# LED_panel_rev3_15.net
KiCad netlist of a schematic drawn in EAGLE
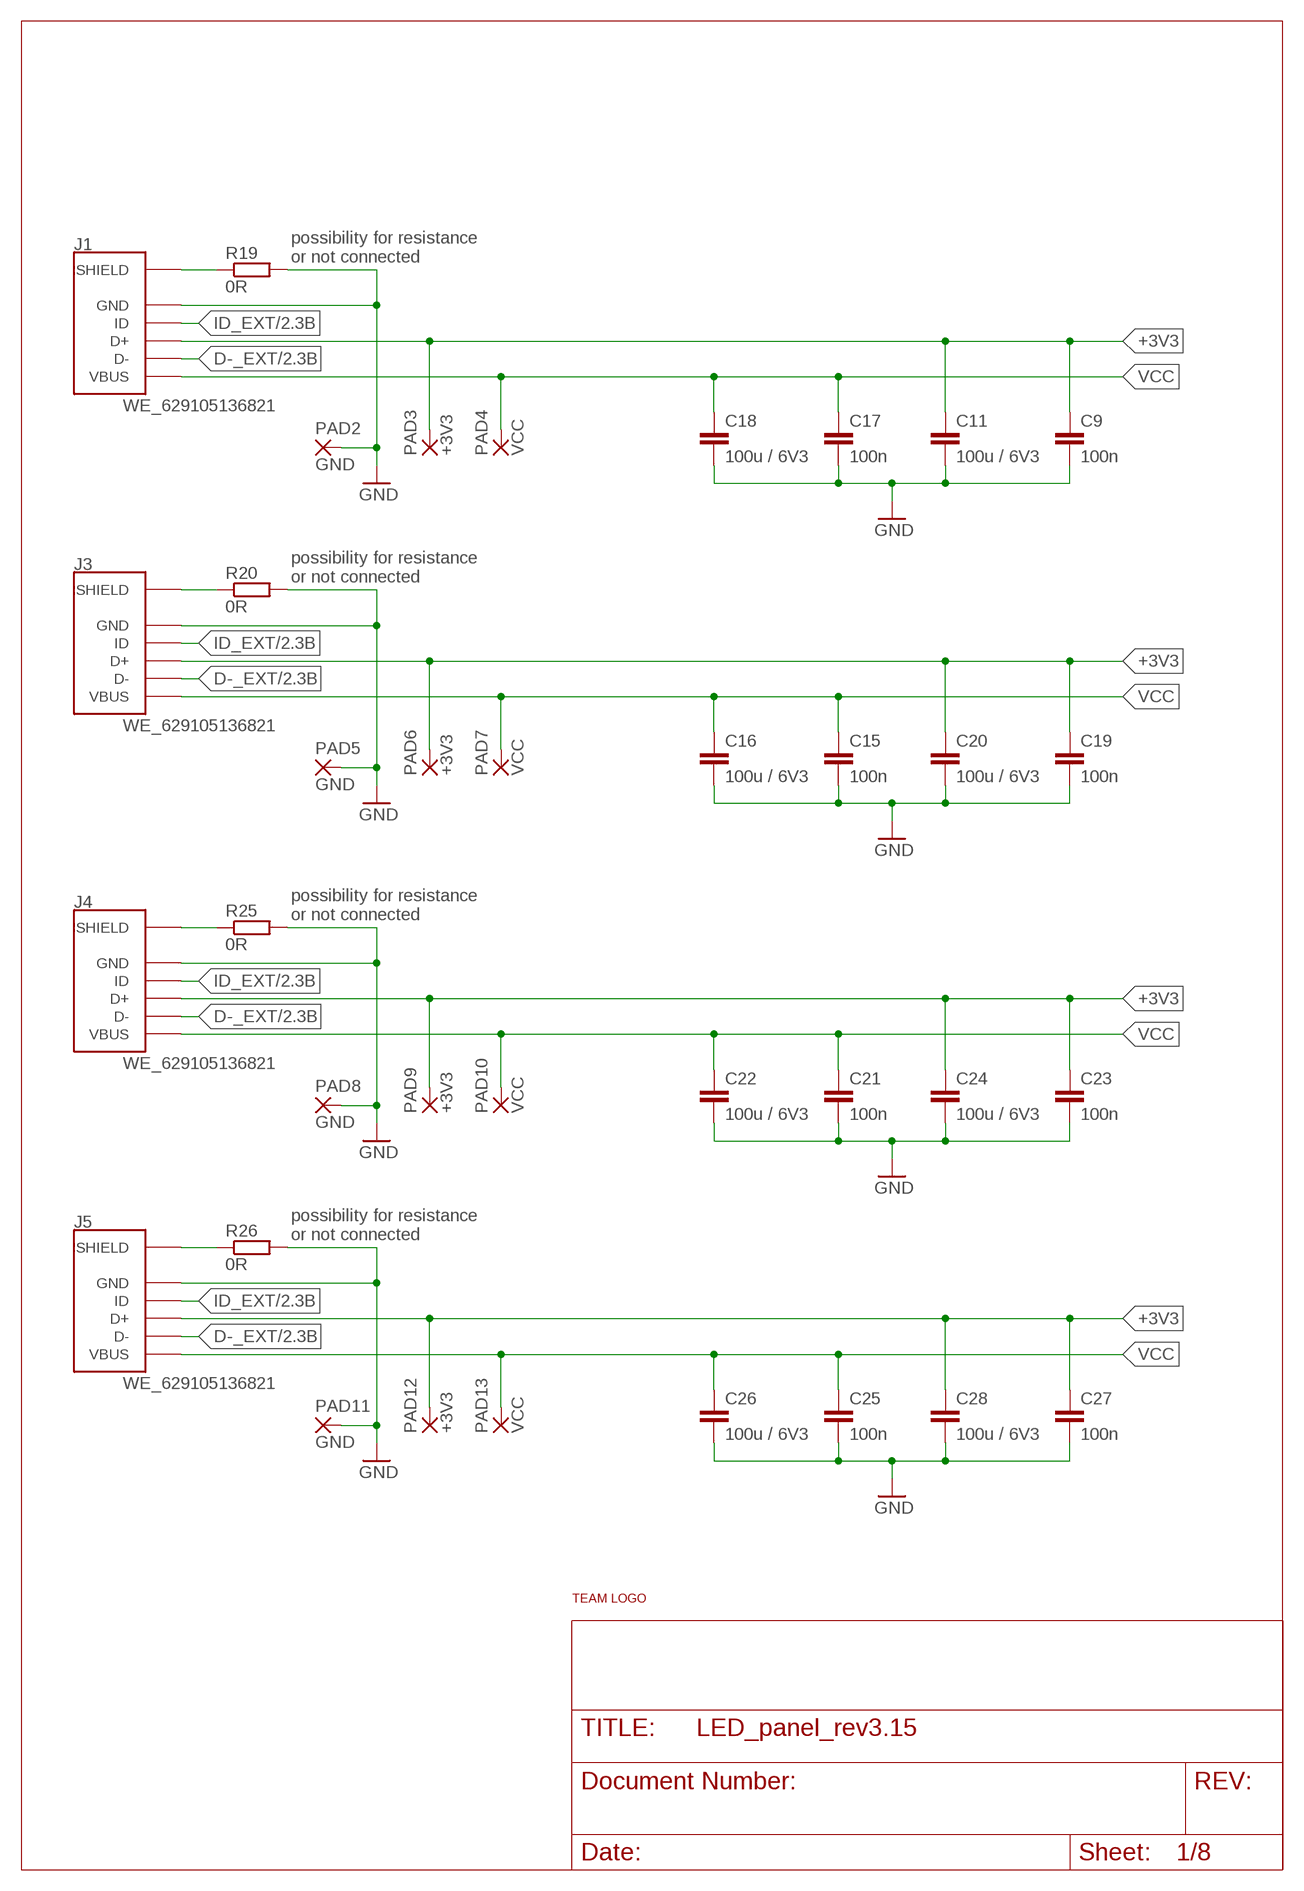
[diagram p0: schematic, sheet 1]
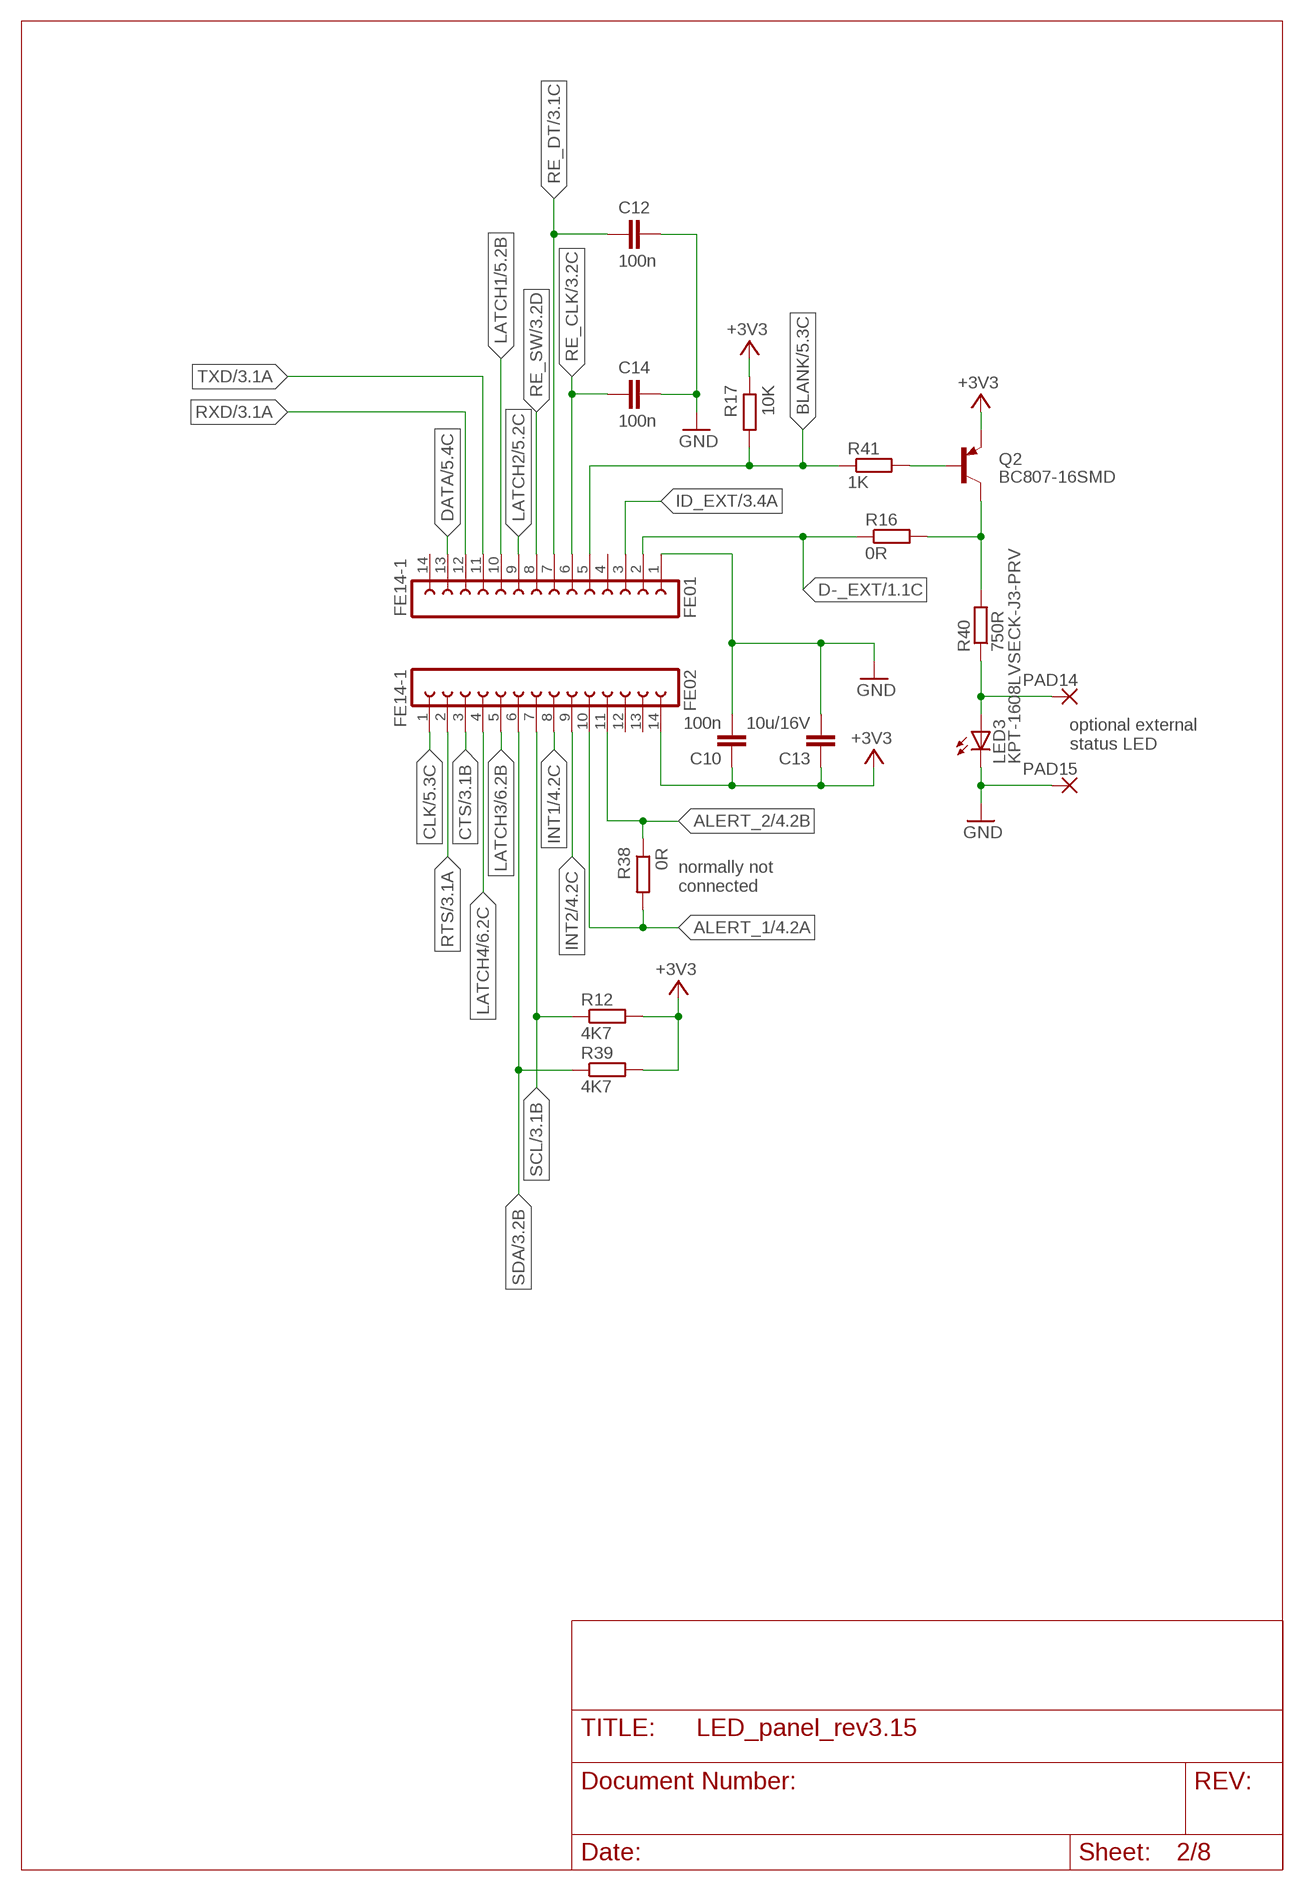
[diagram p1: schematic, sheet 2]
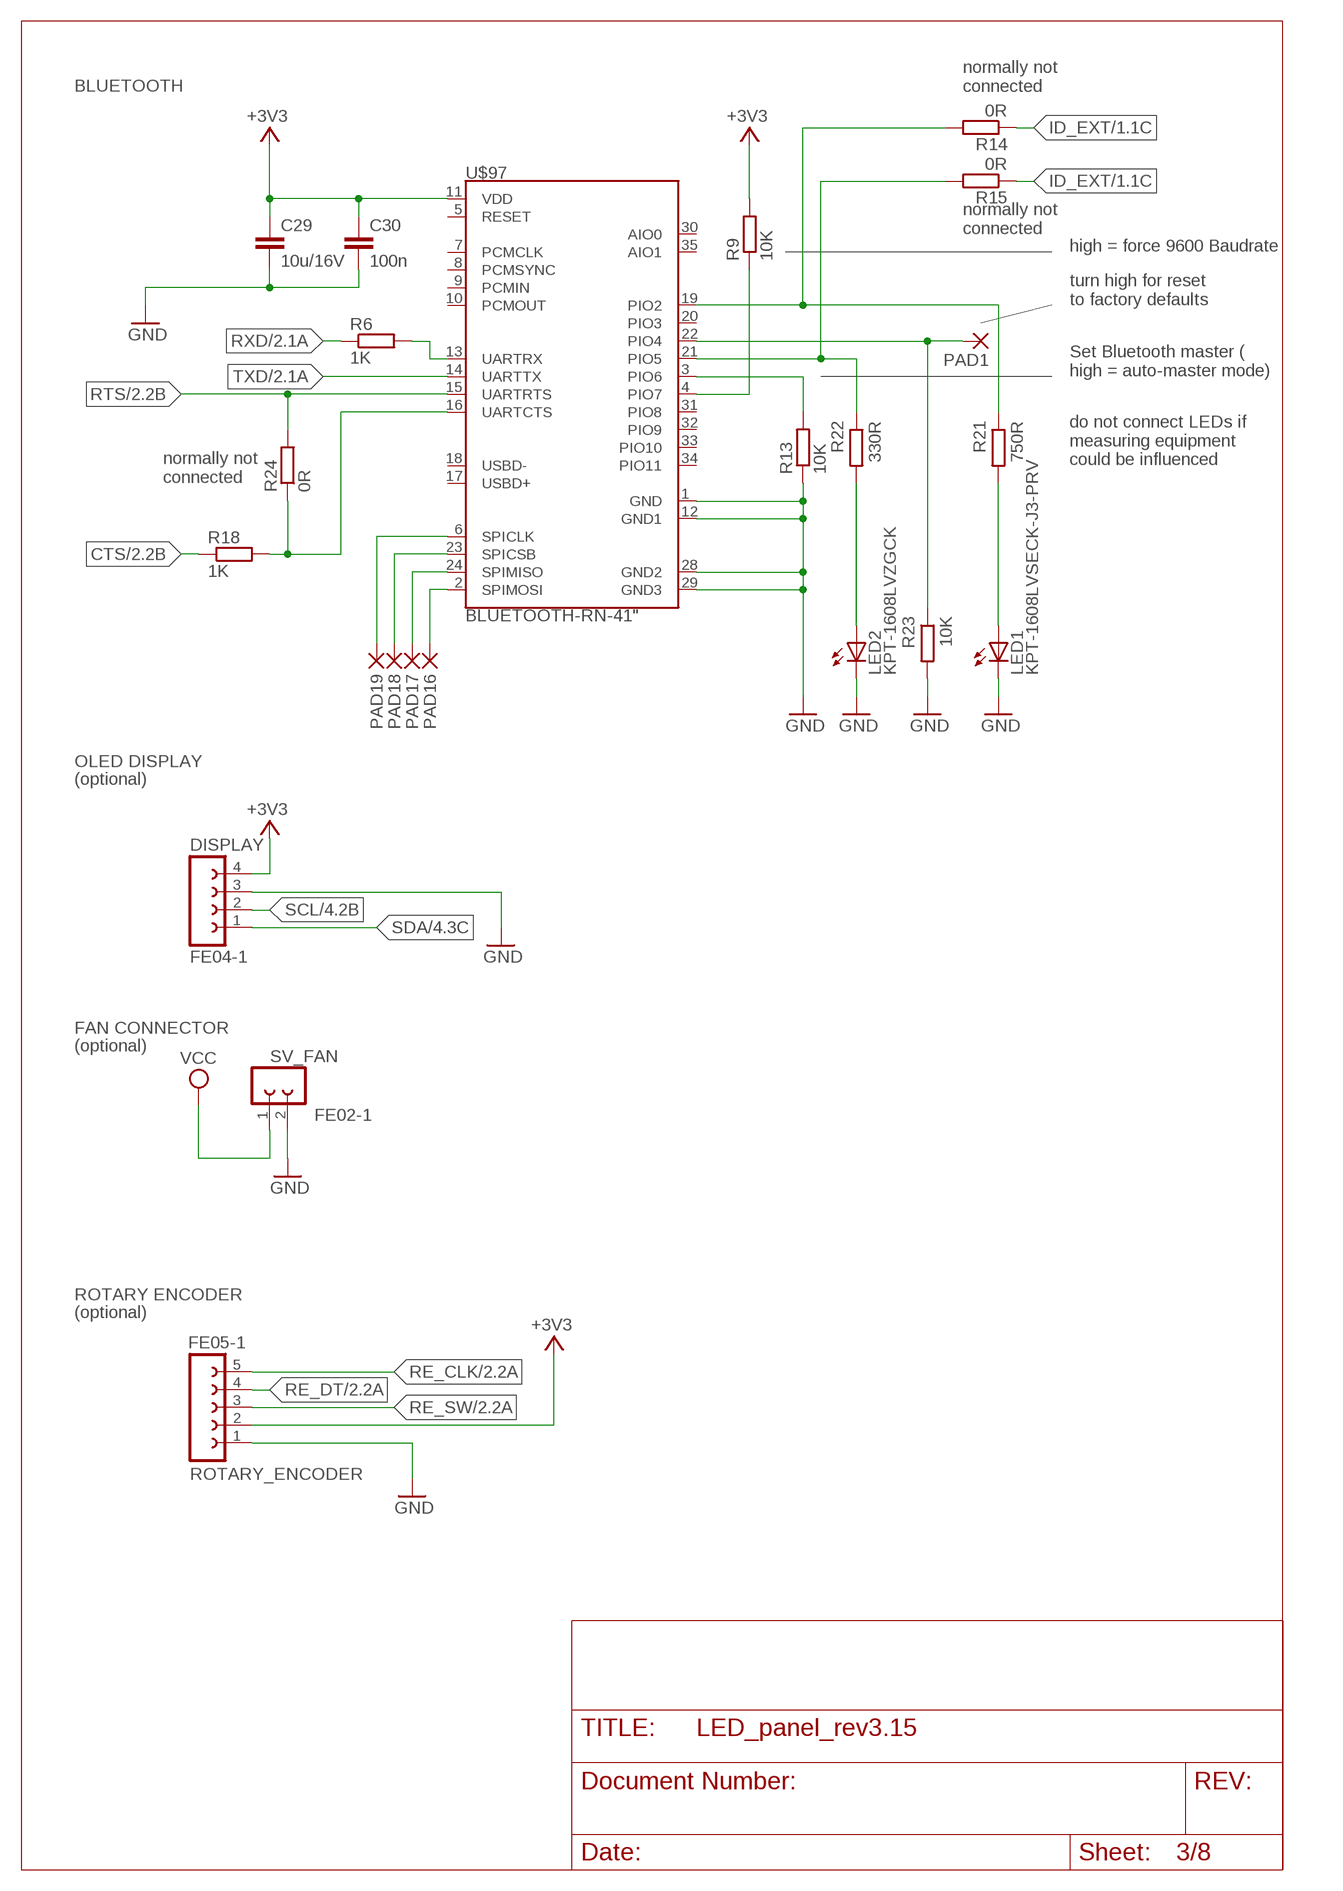
[diagram p2: schematic, sheet 3]
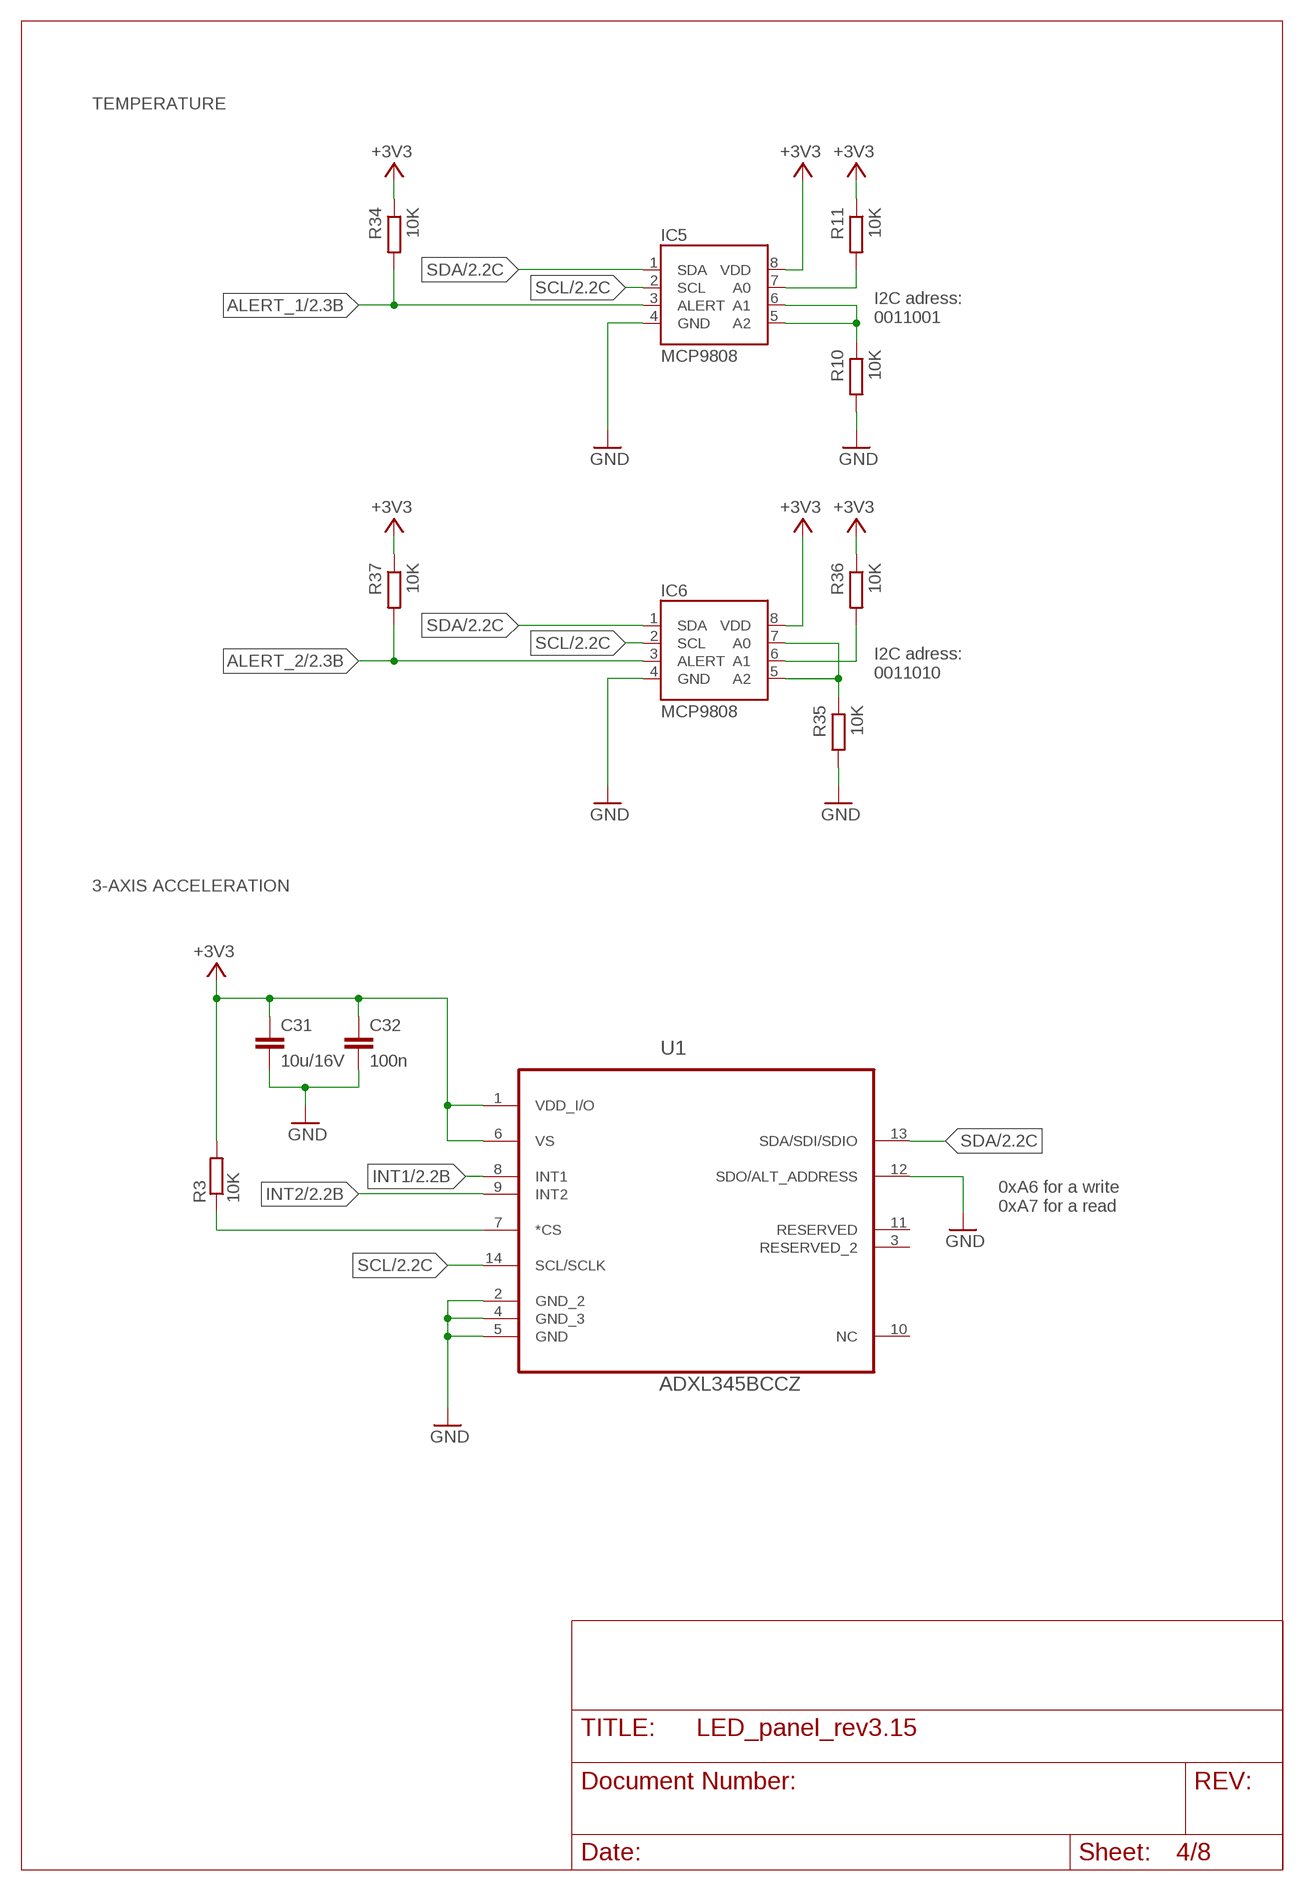
[diagram p3: schematic, sheet 4]
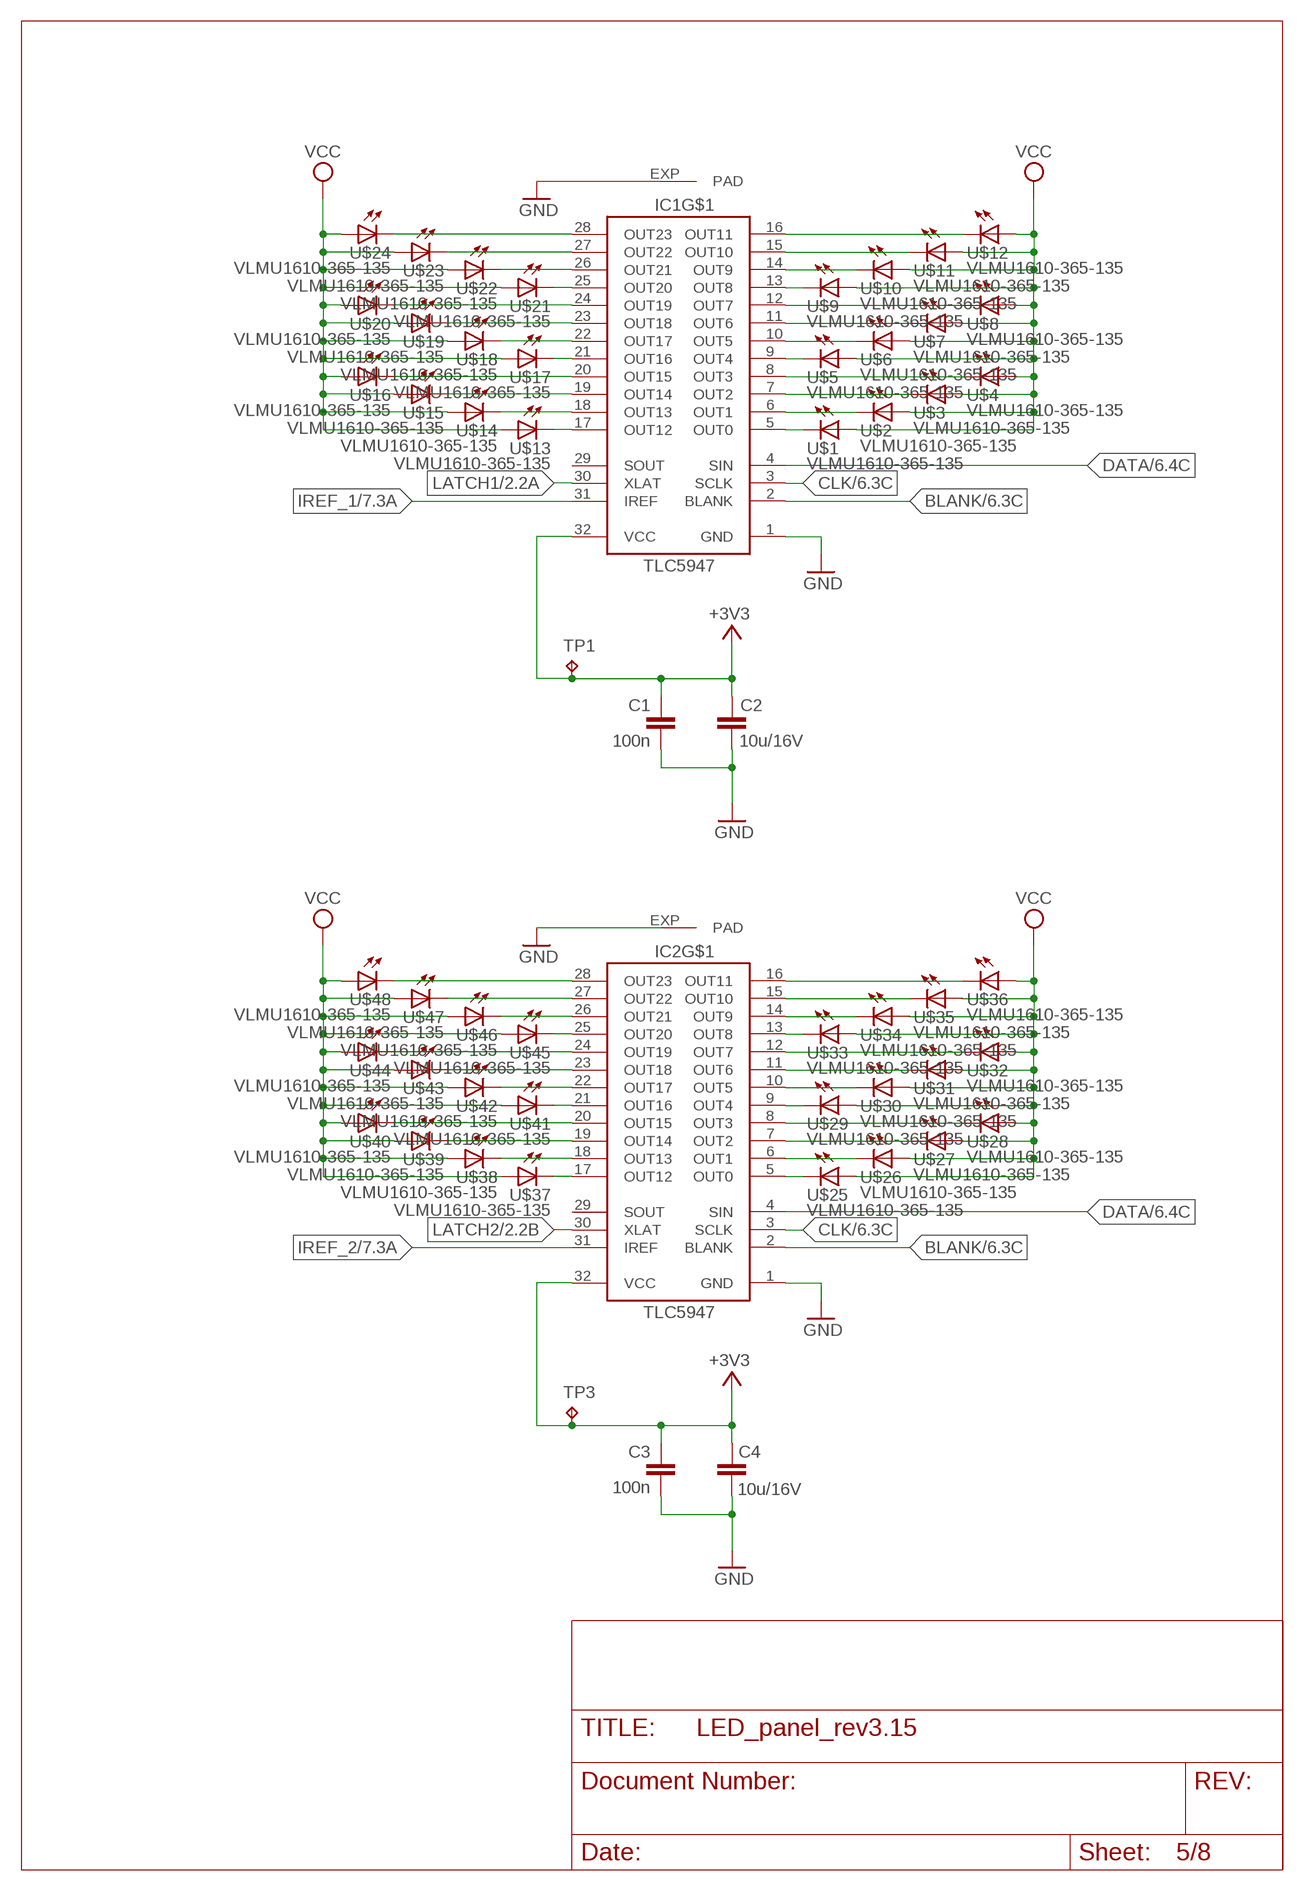
[diagram p4: schematic, sheet 5]
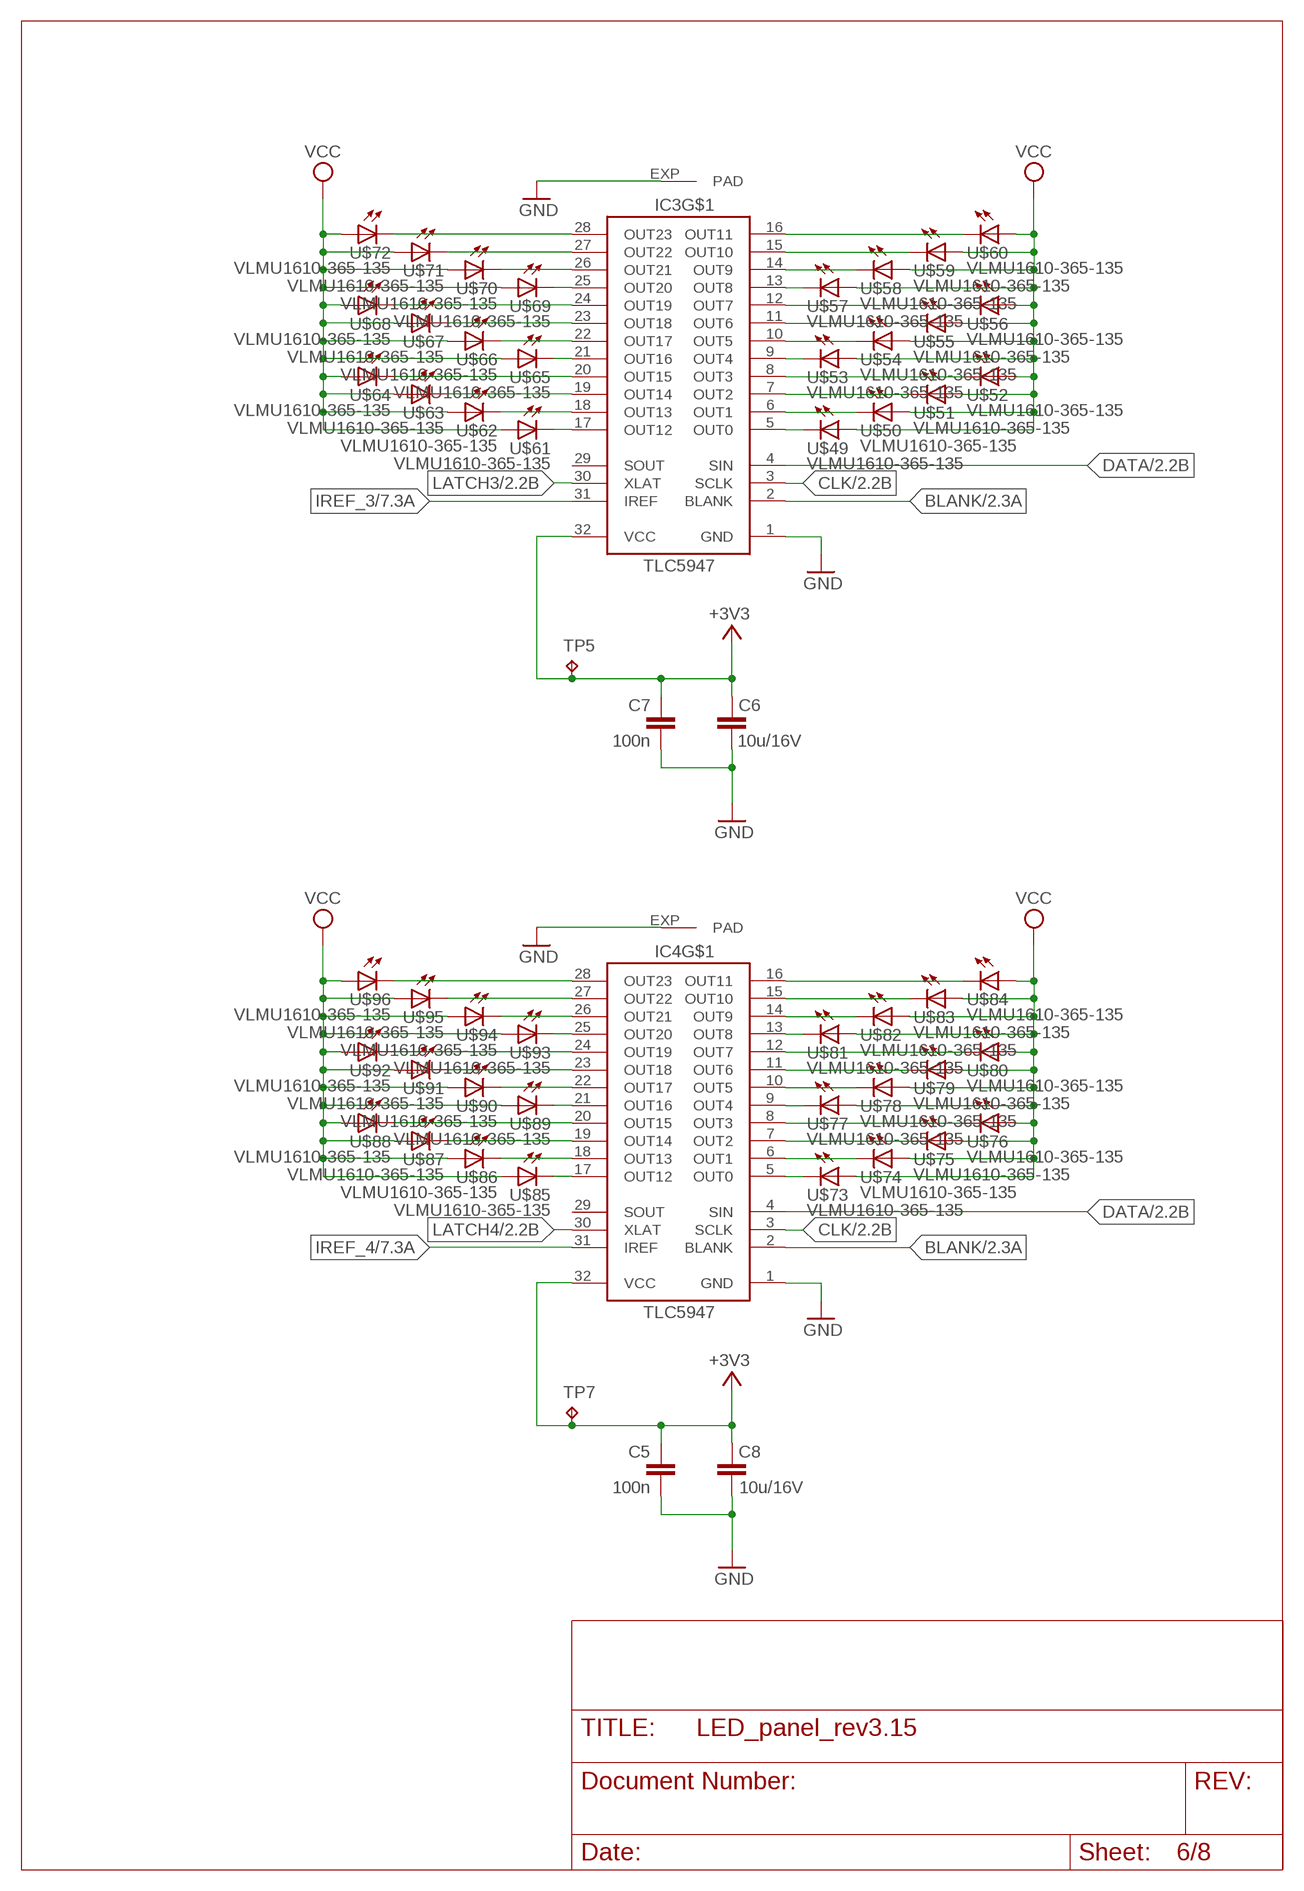
[diagram p5: schematic, sheet 6]
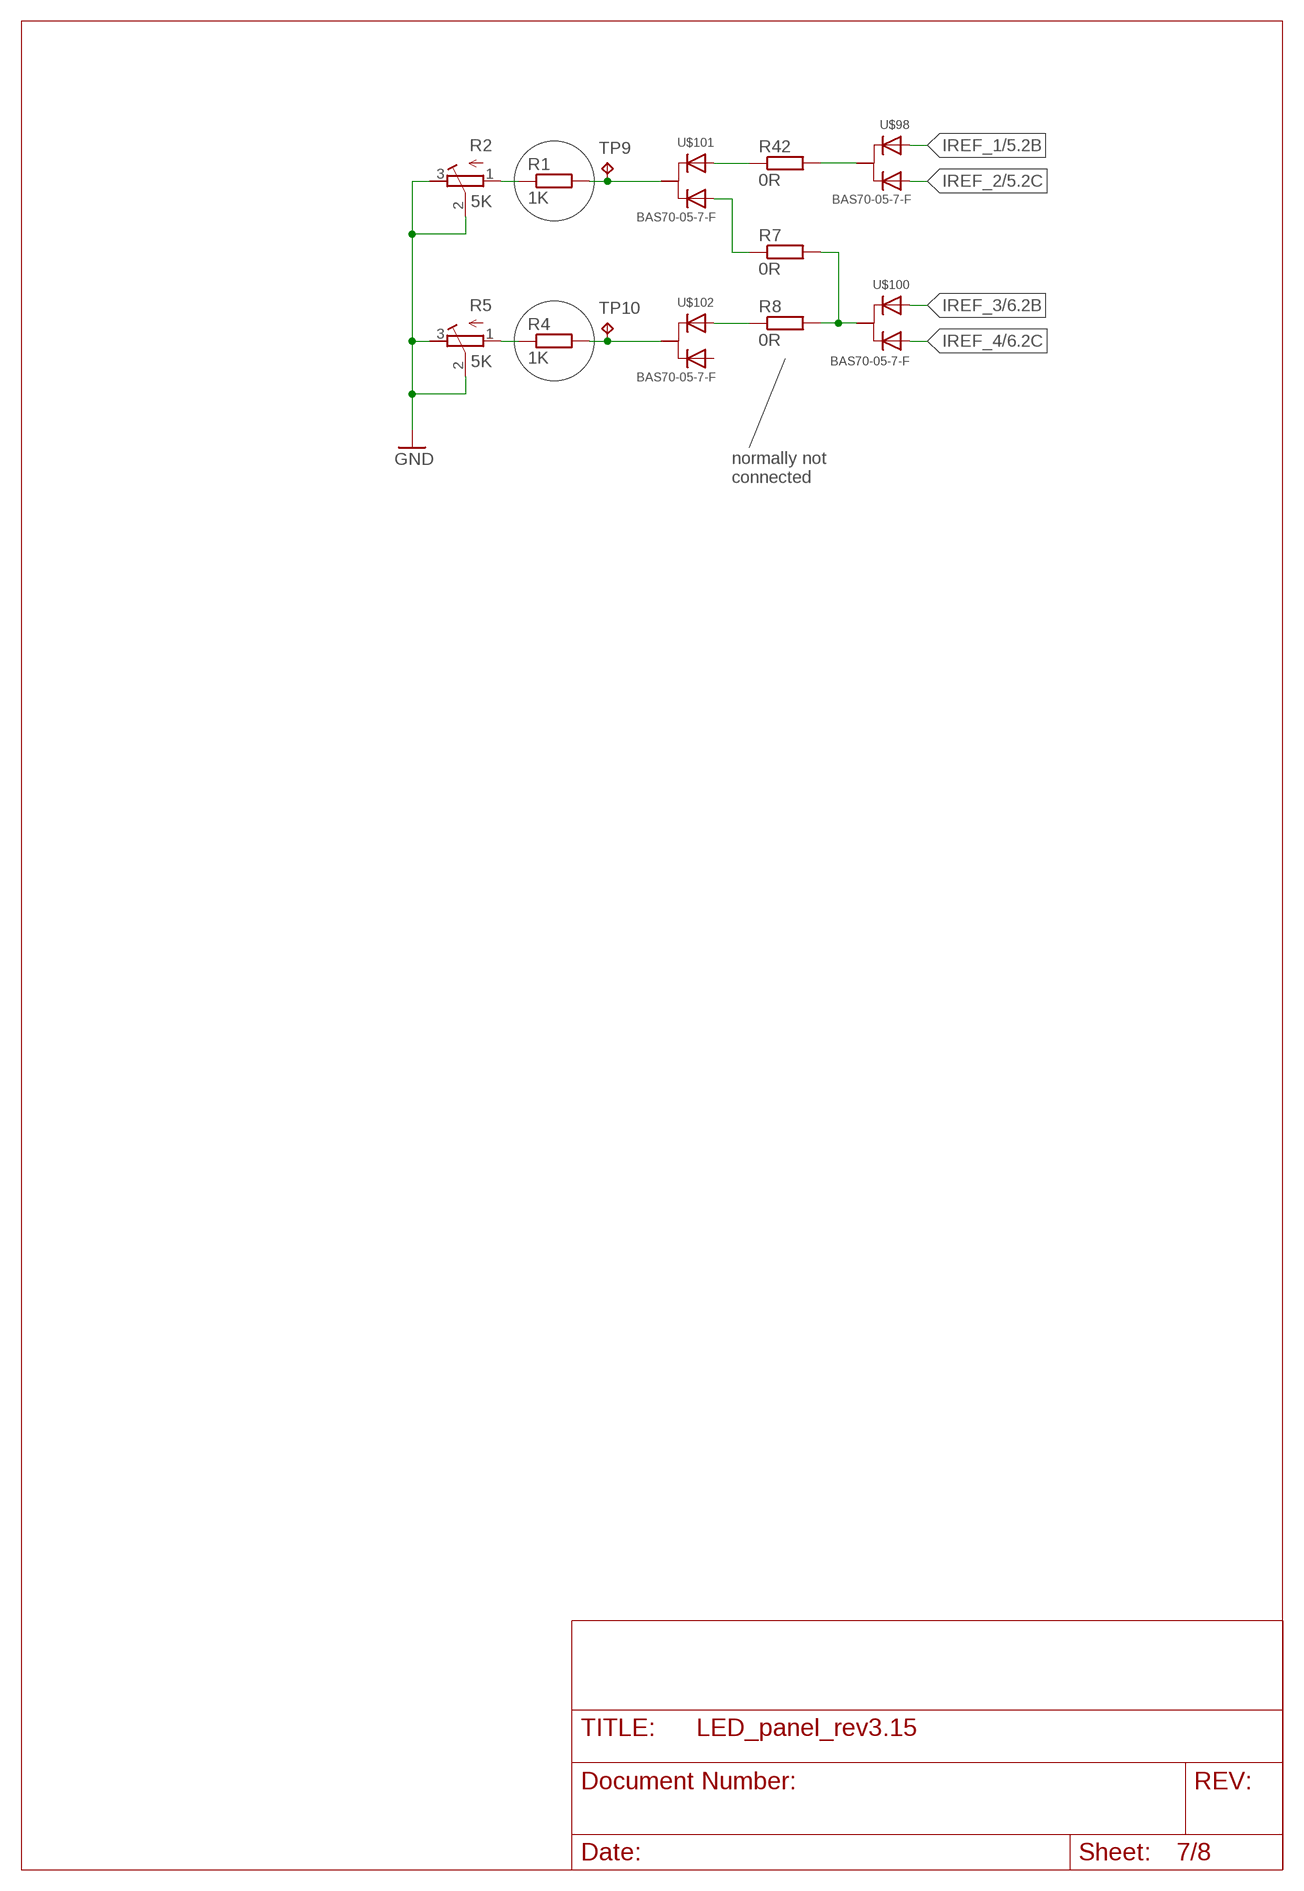
[diagram p6: schematic, sheet 7]

(export (version "E")
  (design (tool "Eeschema 10.0.6"))
  (components
    (comp (ref "C31")
      (value "10u/16V")
      (footprint "eagle-import:C1206K")
      (libsource (lib "eagle-import") (part "C-EUC1206K"))
    )
    (comp (ref "C32")
      (value "100n")
      (footprint "eagle-import:C1206K")
      (libsource (lib "eagle-import") (part "C-EUC1206K"))
    )
    (comp (ref "IC5")
      (value "MCP9808")
      (footprint "eagle-import:MSOP8")
      (libsource (lib "eagle-import") (part "MCP9808"))
    )
    (comp (ref "IC6")
      (value "MCP9808")
      (footprint "eagle-import:MSOP8")
      (libsource (lib "eagle-import") (part "MCP9808"))
    )
    (comp (ref "R3")
      (value "10K")
      (footprint "eagle-import:R1206")
      (libsource (lib "eagle-import") (part "R-EU_R1206"))
    )
    (comp (ref "R10")
      (value "10K")
      (footprint "eagle-import:R1206")
      (libsource (lib "eagle-import") (part "R-EU_R1206"))
    )
    (comp (ref "R11")
      (value "10K")
      (footprint "eagle-import:R1206")
      (libsource (lib "eagle-import") (part "R-EU_R1206"))
    )
    (comp (ref "R34")
      (value "10K")
      (footprint "eagle-import:R1206")
      (libsource (lib "eagle-import") (part "R-EU_R1206"))
    )
    (comp (ref "R35")
      (value "10K")
      (footprint "eagle-import:R1206")
      (libsource (lib "eagle-import") (part "R-EU_R1206"))
    )
    (comp (ref "R36")
      (value "10K")
      (footprint "eagle-import:R1206")
      (libsource (lib "eagle-import") (part "R-EU_R1206"))
    )
    (comp (ref "R37")
      (value "10K")
      (footprint "eagle-import:R1206")
      (libsource (lib "eagle-import") (part "R-EU_R1206"))
    )
    (comp (ref "U1")
      (value "ADXL345BCCZ")
      (footprint "eagle-import:LGA14R80P3X6_300X500X100")
      (libsource (lib "eagle-import") (part "ADXL345BCCZ"))
    )
    (comp (ref "C1")
      (value "100n")
      (footprint "eagle-import:C1206K")
      (libsource (lib "eagle-import") (part "C-EUC1206K"))
    )
    (comp (ref "C2")
      (value "10u/16V")
      (footprint "eagle-import:C1206K")
      (libsource (lib "eagle-import") (part "C-EUC1206K"))
    )
    (comp (ref "C3")
      (value "100n")
      (footprint "eagle-import:C1206K")
      (libsource (lib "eagle-import") (part "C-EUC1206K"))
    )
    (comp (ref "C4")
      (value "10u/16V")
      (footprint "eagle-import:C1206K")
      (libsource (lib "eagle-import") (part "C-EUC1206K"))
    )
    (comp (ref "IC1")
      (value "TLC5947-DAP")
      (footprint "eagle-import:HTSSOP32DAP")
      (libsource (lib "eagle-import") (part "TLC5947-DAP"))
    )
    (comp (ref "IC2")
      (value "TLC5947-DAP")
      (footprint "eagle-import:HTSSOP32DAP")
      (libsource (lib "eagle-import") (part "TLC5947-DAP"))
    )
    (comp (ref "TP1")
      (value "TPTP20R")
      (footprint "eagle-import:TP20R")
      (libsource (lib "eagle-import") (part "TPTP20R"))
    )
    (comp (ref "TP3")
      (value "TPTP20R")
      (footprint "eagle-import:TP20R")
      (libsource (lib "eagle-import") (part "TPTP20R"))
    )
    (comp (ref "U$1")
      (value "VLMU1610-365-135")
      (footprint "eagle-import:SMD_CERAMIC_MID_POWER")
      (libsource (lib "eagle-import") (part "VLMU1610-365-135"))
    )
    (comp (ref "U$2")
      (value "VLMU1610-365-135")
      (footprint "eagle-import:SMD_CERAMIC_MID_POWER")
      (libsource (lib "eagle-import") (part "VLMU1610-365-135"))
    )
    (comp (ref "U$3")
      (value "VLMU1610-365-135")
      (footprint "eagle-import:SMD_CERAMIC_MID_POWER")
      (libsource (lib "eagle-import") (part "VLMU1610-365-135"))
    )
    (comp (ref "U$4")
      (value "VLMU1610-365-135")
      (footprint "eagle-import:SMD_CERAMIC_MID_POWER")
      (libsource (lib "eagle-import") (part "VLMU1610-365-135"))
    )
    (comp (ref "U$5")
      (value "VLMU1610-365-135")
      (footprint "eagle-import:SMD_CERAMIC_MID_POWER")
      (libsource (lib "eagle-import") (part "VLMU1610-365-135"))
    )
    (comp (ref "U$6")
      (value "VLMU1610-365-135")
      (footprint "eagle-import:SMD_CERAMIC_MID_POWER")
      (libsource (lib "eagle-import") (part "VLMU1610-365-135"))
    )
    (comp (ref "U$7")
      (value "VLMU1610-365-135")
      (footprint "eagle-import:SMD_CERAMIC_MID_POWER")
      (libsource (lib "eagle-import") (part "VLMU1610-365-135"))
    )
    (comp (ref "U$8")
      (value "VLMU1610-365-135")
      (footprint "eagle-import:SMD_CERAMIC_MID_POWER")
      (libsource (lib "eagle-import") (part "VLMU1610-365-135"))
    )
    (comp (ref "U$9")
      (value "VLMU1610-365-135")
      (footprint "eagle-import:SMD_CERAMIC_MID_POWER")
      (libsource (lib "eagle-import") (part "VLMU1610-365-135"))
    )
    (comp (ref "U$10")
      (value "VLMU1610-365-135")
      (footprint "eagle-import:SMD_CERAMIC_MID_POWER")
      (libsource (lib "eagle-import") (part "VLMU1610-365-135"))
    )
    (comp (ref "U$11")
      (value "VLMU1610-365-135")
      (footprint "eagle-import:SMD_CERAMIC_MID_POWER")
      (libsource (lib "eagle-import") (part "VLMU1610-365-135"))
    )
    (comp (ref "U$12")
      (value "VLMU1610-365-135")
      (footprint "eagle-import:SMD_CERAMIC_MID_POWER")
      (libsource (lib "eagle-import") (part "VLMU1610-365-135"))
    )
    (comp (ref "U$13")
      (value "VLMU1610-365-135")
      (footprint "eagle-import:SMD_CERAMIC_MID_POWER")
      (libsource (lib "eagle-import") (part "VLMU1610-365-135"))
    )
    (comp (ref "U$14")
      (value "VLMU1610-365-135")
      (footprint "eagle-import:SMD_CERAMIC_MID_POWER")
      (libsource (lib "eagle-import") (part "VLMU1610-365-135"))
    )
    (comp (ref "U$15")
      (value "VLMU1610-365-135")
      (footprint "eagle-import:SMD_CERAMIC_MID_POWER")
      (libsource (lib "eagle-import") (part "VLMU1610-365-135"))
    )
    (comp (ref "U$16")
      (value "VLMU1610-365-135")
      (footprint "eagle-import:SMD_CERAMIC_MID_POWER")
      (libsource (lib "eagle-import") (part "VLMU1610-365-135"))
    )
    (comp (ref "U$17")
      (value "VLMU1610-365-135")
      (footprint "eagle-import:SMD_CERAMIC_MID_POWER")
      (libsource (lib "eagle-import") (part "VLMU1610-365-135"))
    )
    (comp (ref "U$18")
      (value "VLMU1610-365-135")
      (footprint "eagle-import:SMD_CERAMIC_MID_POWER")
      (libsource (lib "eagle-import") (part "VLMU1610-365-135"))
    )
    (comp (ref "U$19")
      (value "VLMU1610-365-135")
      (footprint "eagle-import:SMD_CERAMIC_MID_POWER")
      (libsource (lib "eagle-import") (part "VLMU1610-365-135"))
    )
    (comp (ref "U$20")
      (value "VLMU1610-365-135")
      (footprint "eagle-import:SMD_CERAMIC_MID_POWER")
      (libsource (lib "eagle-import") (part "VLMU1610-365-135"))
    )
    (comp (ref "U$21")
      (value "VLMU1610-365-135")
      (footprint "eagle-import:SMD_CERAMIC_MID_POWER")
      (libsource (lib "eagle-import") (part "VLMU1610-365-135"))
    )
    (comp (ref "U$22")
      (value "VLMU1610-365-135")
      (footprint "eagle-import:SMD_CERAMIC_MID_POWER")
      (libsource (lib "eagle-import") (part "VLMU1610-365-135"))
    )
    (comp (ref "U$23")
      (value "VLMU1610-365-135")
      (footprint "eagle-import:SMD_CERAMIC_MID_POWER")
      (libsource (lib "eagle-import") (part "VLMU1610-365-135"))
    )
    (comp (ref "U$24")
      (value "VLMU1610-365-135")
      (footprint "eagle-import:SMD_CERAMIC_MID_POWER")
      (libsource (lib "eagle-import") (part "VLMU1610-365-135"))
    )
    (comp (ref "U$25")
      (value "VLMU1610-365-135")
      (footprint "eagle-import:SMD_CERAMIC_MID_POWER")
      (libsource (lib "eagle-import") (part "VLMU1610-365-135"))
    )
    (comp (ref "U$26")
      (value "VLMU1610-365-135")
      (footprint "eagle-import:SMD_CERAMIC_MID_POWER")
      (libsource (lib "eagle-import") (part "VLMU1610-365-135"))
    )
    (comp (ref "U$27")
      (value "VLMU1610-365-135")
      (footprint "eagle-import:SMD_CERAMIC_MID_POWER")
      (libsource (lib "eagle-import") (part "VLMU1610-365-135"))
    )
    (comp (ref "U$28")
      (value "VLMU1610-365-135")
      (footprint "eagle-import:SMD_CERAMIC_MID_POWER")
      (libsource (lib "eagle-import") (part "VLMU1610-365-135"))
    )
    (comp (ref "U$29")
      (value "VLMU1610-365-135")
      (footprint "eagle-import:SMD_CERAMIC_MID_POWER")
      (libsource (lib "eagle-import") (part "VLMU1610-365-135"))
    )
    (comp (ref "U$30")
      (value "VLMU1610-365-135")
      (footprint "eagle-import:SMD_CERAMIC_MID_POWER")
      (libsource (lib "eagle-import") (part "VLMU1610-365-135"))
    )
    (comp (ref "U$31")
      (value "VLMU1610-365-135")
      (footprint "eagle-import:SMD_CERAMIC_MID_POWER")
      (libsource (lib "eagle-import") (part "VLMU1610-365-135"))
    )
    (comp (ref "U$32")
      (value "VLMU1610-365-135")
      (footprint "eagle-import:SMD_CERAMIC_MID_POWER")
      (libsource (lib "eagle-import") (part "VLMU1610-365-135"))
    )
    (comp (ref "U$33")
      (value "VLMU1610-365-135")
      (footprint "eagle-import:SMD_CERAMIC_MID_POWER")
      (libsource (lib "eagle-import") (part "VLMU1610-365-135"))
    )
    (comp (ref "U$34")
      (value "VLMU1610-365-135")
      (footprint "eagle-import:SMD_CERAMIC_MID_POWER")
      (libsource (lib "eagle-import") (part "VLMU1610-365-135"))
    )
    (comp (ref "U$35")
      (value "VLMU1610-365-135")
      (footprint "eagle-import:SMD_CERAMIC_MID_POWER")
      (libsource (lib "eagle-import") (part "VLMU1610-365-135"))
    )
    (comp (ref "U$36")
      (value "VLMU1610-365-135")
      (footprint "eagle-import:SMD_CERAMIC_MID_POWER")
      (libsource (lib "eagle-import") (part "VLMU1610-365-135"))
    )
    (comp (ref "U$37")
      (value "VLMU1610-365-135")
      (footprint "eagle-import:SMD_CERAMIC_MID_POWER")
      (libsource (lib "eagle-import") (part "VLMU1610-365-135"))
    )
    (comp (ref "U$38")
      (value "VLMU1610-365-135")
      (footprint "eagle-import:SMD_CERAMIC_MID_POWER")
      (libsource (lib "eagle-import") (part "VLMU1610-365-135"))
    )
    (comp (ref "U$39")
      (value "VLMU1610-365-135")
      (footprint "eagle-import:SMD_CERAMIC_MID_POWER")
      (libsource (lib "eagle-import") (part "VLMU1610-365-135"))
    )
    (comp (ref "U$40")
      (value "VLMU1610-365-135")
      (footprint "eagle-import:SMD_CERAMIC_MID_POWER")
      (libsource (lib "eagle-import") (part "VLMU1610-365-135"))
    )
    (comp (ref "U$41")
      (value "VLMU1610-365-135")
      (footprint "eagle-import:SMD_CERAMIC_MID_POWER")
      (libsource (lib "eagle-import") (part "VLMU1610-365-135"))
    )
    (comp (ref "U$42")
      (value "VLMU1610-365-135")
      (footprint "eagle-import:SMD_CERAMIC_MID_POWER")
      (libsource (lib "eagle-import") (part "VLMU1610-365-135"))
    )
    (comp (ref "U$43")
      (value "VLMU1610-365-135")
      (footprint "eagle-import:SMD_CERAMIC_MID_POWER")
      (libsource (lib "eagle-import") (part "VLMU1610-365-135"))
    )
    (comp (ref "U$44")
      (value "VLMU1610-365-135")
      (footprint "eagle-import:SMD_CERAMIC_MID_POWER")
      (libsource (lib "eagle-import") (part "VLMU1610-365-135"))
    )
    (comp (ref "U$45")
      (value "VLMU1610-365-135")
      (footprint "eagle-import:SMD_CERAMIC_MID_POWER")
      (libsource (lib "eagle-import") (part "VLMU1610-365-135"))
    )
    (comp (ref "U$46")
      (value "VLMU1610-365-135")
      (footprint "eagle-import:SMD_CERAMIC_MID_POWER")
      (libsource (lib "eagle-import") (part "VLMU1610-365-135"))
    )
    (comp (ref "U$47")
      (value "VLMU1610-365-135")
      (footprint "eagle-import:SMD_CERAMIC_MID_POWER")
      (libsource (lib "eagle-import") (part "VLMU1610-365-135"))
    )
    (comp (ref "U$48")
      (value "VLMU1610-365-135")
      (footprint "eagle-import:SMD_CERAMIC_MID_POWER")
      (libsource (lib "eagle-import") (part "VLMU1610-365-135"))
    )
    (comp (ref "C10")
      (value "100n")
      (footprint "eagle-import:C1206K")
      (libsource (lib "eagle-import") (part "C-EUC1206K"))
    )
    (comp (ref "C12")
      (value "100n")
      (footprint "eagle-import:C1206K")
      (libsource (lib "eagle-import") (part "C-EUC1206K"))
    )
    (comp (ref "C13")
      (value "10u/16V")
      (footprint "eagle-import:C1206K")
      (libsource (lib "eagle-import") (part "C-EUC1206K"))
    )
    (comp (ref "C14")
      (value "100n")
      (footprint "eagle-import:C1206K")
      (libsource (lib "eagle-import") (part "C-EUC1206K"))
    )
    (comp (ref "FE01")
      (value "FE14-1")
      (footprint "eagle-import:FE14")
      (libsource (lib "eagle-import") (part "FE14-1"))
    )
    (comp (ref "FE02")
      (value "FE14-1")
      (footprint "eagle-import:FE14")
      (libsource (lib "eagle-import") (part "FE14-1"))
    )
    (comp (ref "LED3")
      (value "KPT-1608LVSECK-J3-PRV")
      (footprint "eagle-import:MH_KINGBRIGHT_1.6X0.8")
      (libsource (lib "eagle-import") (part "KPT-1608LVSECK-J3-PRV"))
    )
    (comp (ref "PAD14")
      (value "2,54/1,0")
      (footprint "eagle-import:2,54_1,0")
      (libsource (lib "eagle-import") (part "2,54/1,0"))
    )
    (comp (ref "PAD15")
      (value "2,54/1,0")
      (footprint "eagle-import:2,54_1,0")
      (libsource (lib "eagle-import") (part "2,54/1,0"))
    )
    (comp (ref "Q2")
      (value "BC807-16SMD")
      (footprint "eagle-import:SOT23-BEC")
      (libsource (lib "eagle-import") (part "BC807SMD-16"))
    )
    (comp (ref "R12")
      (value "4K7")
      (footprint "eagle-import:R1206")
      (libsource (lib "eagle-import") (part "R-EU_R1206"))
    )
    (comp (ref "R16")
      (value "0R")
      (footprint "eagle-import:R1206")
      (libsource (lib "eagle-import") (part "R-EU_R1206"))
    )
    (comp (ref "R17")
      (value "10K")
      (footprint "eagle-import:R1206")
      (libsource (lib "eagle-import") (part "R-EU_R1206"))
    )
    (comp (ref "R38")
      (value "0R")
      (footprint "eagle-import:R1206")
      (libsource (lib "eagle-import") (part "R-EU_R1206"))
    )
    (comp (ref "R39")
      (value "4K7")
      (footprint "eagle-import:R1206")
      (libsource (lib "eagle-import") (part "R-EU_R1206"))
    )
    (comp (ref "R40")
      (value "750R")
      (footprint "eagle-import:R1206")
      (libsource (lib "eagle-import") (part "R-EU_R1206"))
    )
    (comp (ref "R41")
      (value "1K")
      (footprint "eagle-import:R1206")
      (libsource (lib "eagle-import") (part "R-EU_R1206"))
    )
    (comp (ref "R1")
      (value "1K")
      (footprint "eagle-import:R1206")
      (libsource (lib "eagle-import") (part "R-EU_R1206"))
    )
    (comp (ref "R2")
      (value "5K")
      (footprint "eagle-import:RTRIM4G_J")
      (libsource (lib "eagle-import") (part "R-TRIMM4G/J"))
    )
    (comp (ref "R4")
      (value "1K")
      (footprint "eagle-import:R1206")
      (libsource (lib "eagle-import") (part "R-EU_R1206"))
    )
    (comp (ref "R5")
      (value "5K")
      (footprint "eagle-import:RTRIM4G_J")
      (libsource (lib "eagle-import") (part "R-TRIMM4G/J"))
    )
    (comp (ref "R7")
      (value "0R")
      (footprint "eagle-import:R1206")
      (libsource (lib "eagle-import") (part "R-EU_R1206"))
    )
    (comp (ref "R8")
      (value "0R")
      (footprint "eagle-import:R1206")
      (libsource (lib "eagle-import") (part "R-EU_R1206"))
    )
    (comp (ref "R42")
      (value "0R")
      (footprint "eagle-import:R1206")
      (libsource (lib "eagle-import") (part "R-EU_R1206"))
    )
    (comp (ref "TP9")
      (value "TPTP20R")
      (footprint "eagle-import:TP20R")
      (libsource (lib "eagle-import") (part "TPTP20R"))
    )
    (comp (ref "TP10")
      (value "TPTP20R")
      (footprint "eagle-import:TP20R")
      (libsource (lib "eagle-import") (part "TPTP20R"))
    )
    (comp (ref "U$98")
      (value "BAS70-05-7-F")
      (footprint "eagle-import:SOT23")
      (libsource (lib "eagle-import") (part "BAS70-05-7-F"))
    )
    (comp (ref "U$100")
      (value "BAS70-05-7-F")
      (footprint "eagle-import:SOT23")
      (libsource (lib "eagle-import") (part "BAS70-05-7-F"))
    )
    (comp (ref "U$101")
      (value "BAS70-05-7-F")
      (footprint "eagle-import:SOT23")
      (libsource (lib "eagle-import") (part "BAS70-05-7-F"))
    )
    (comp (ref "U$102")
      (value "BAS70-05-7-F")
      (footprint "eagle-import:SOT23")
      (libsource (lib "eagle-import") (part "BAS70-05-7-F"))
    )
    (comp (ref "C5")
      (value "100n")
      (footprint "eagle-import:C1206K")
      (libsource (lib "eagle-import") (part "C-EUC1206K"))
    )
    (comp (ref "C6")
      (value "10u/16V")
      (footprint "eagle-import:C1206K")
      (libsource (lib "eagle-import") (part "C-EUC1206K"))
    )
    (comp (ref "C7")
      (value "100n")
      (footprint "eagle-import:C1206K")
      (libsource (lib "eagle-import") (part "C-EUC1206K"))
    )
    (comp (ref "C8")
      (value "10u/16V")
      (footprint "eagle-import:C1206K")
      (libsource (lib "eagle-import") (part "C-EUC1206K"))
    )
    (comp (ref "IC3")
      (value "TLC5947-DAP")
      (footprint "eagle-import:HTSSOP32DAP")
      (libsource (lib "eagle-import") (part "TLC5947-DAP"))
    )
    (comp (ref "IC4")
      (value "TLC5947-DAP")
      (footprint "eagle-import:HTSSOP32DAP")
      (libsource (lib "eagle-import") (part "TLC5947-DAP"))
    )
    (comp (ref "TP5")
      (value "TPTP20R")
      (footprint "eagle-import:TP20R")
      (libsource (lib "eagle-import") (part "TPTP20R"))
    )
    (comp (ref "TP7")
      (value "TPTP20R")
      (footprint "eagle-import:TP20R")
      (libsource (lib "eagle-import") (part "TPTP20R"))
    )
    (comp (ref "U$49")
      (value "VLMU1610-365-135")
      (footprint "eagle-import:SMD_CERAMIC_MID_POWER")
      (libsource (lib "eagle-import") (part "VLMU1610-365-135"))
    )
    (comp (ref "U$50")
      (value "VLMU1610-365-135")
      (footprint "eagle-import:SMD_CERAMIC_MID_POWER")
      (libsource (lib "eagle-import") (part "VLMU1610-365-135"))
    )
    (comp (ref "U$51")
      (value "VLMU1610-365-135")
      (footprint "eagle-import:SMD_CERAMIC_MID_POWER")
      (libsource (lib "eagle-import") (part "VLMU1610-365-135"))
    )
    (comp (ref "U$52")
      (value "VLMU1610-365-135")
      (footprint "eagle-import:SMD_CERAMIC_MID_POWER")
      (libsource (lib "eagle-import") (part "VLMU1610-365-135"))
    )
    (comp (ref "U$53")
      (value "VLMU1610-365-135")
      (footprint "eagle-import:SMD_CERAMIC_MID_POWER")
      (libsource (lib "eagle-import") (part "VLMU1610-365-135"))
    )
    (comp (ref "U$54")
      (value "VLMU1610-365-135")
      (footprint "eagle-import:SMD_CERAMIC_MID_POWER")
      (libsource (lib "eagle-import") (part "VLMU1610-365-135"))
    )
    (comp (ref "U$55")
      (value "VLMU1610-365-135")
      (footprint "eagle-import:SMD_CERAMIC_MID_POWER")
      (libsource (lib "eagle-import") (part "VLMU1610-365-135"))
    )
    (comp (ref "U$56")
      (value "VLMU1610-365-135")
      (footprint "eagle-import:SMD_CERAMIC_MID_POWER")
      (libsource (lib "eagle-import") (part "VLMU1610-365-135"))
    )
    (comp (ref "U$57")
      (value "VLMU1610-365-135")
      (footprint "eagle-import:SMD_CERAMIC_MID_POWER")
      (libsource (lib "eagle-import") (part "VLMU1610-365-135"))
    )
    (comp (ref "U$58")
      (value "VLMU1610-365-135")
      (footprint "eagle-import:SMD_CERAMIC_MID_POWER")
      (libsource (lib "eagle-import") (part "VLMU1610-365-135"))
    )
    (comp (ref "U$59")
      (value "VLMU1610-365-135")
      (footprint "eagle-import:SMD_CERAMIC_MID_POWER")
      (libsource (lib "eagle-import") (part "VLMU1610-365-135"))
    )
    (comp (ref "U$60")
      (value "VLMU1610-365-135")
      (footprint "eagle-import:SMD_CERAMIC_MID_POWER")
      (libsource (lib "eagle-import") (part "VLMU1610-365-135"))
    )
    (comp (ref "U$61")
      (value "VLMU1610-365-135")
      (footprint "eagle-import:SMD_CERAMIC_MID_POWER")
      (libsource (lib "eagle-import") (part "VLMU1610-365-135"))
    )
    (comp (ref "U$62")
      (value "VLMU1610-365-135")
      (footprint "eagle-import:SMD_CERAMIC_MID_POWER")
      (libsource (lib "eagle-import") (part "VLMU1610-365-135"))
    )
    (comp (ref "U$63")
      (value "VLMU1610-365-135")
      (footprint "eagle-import:SMD_CERAMIC_MID_POWER")
      (libsource (lib "eagle-import") (part "VLMU1610-365-135"))
    )
    (comp (ref "U$64")
      (value "VLMU1610-365-135")
      (footprint "eagle-import:SMD_CERAMIC_MID_POWER")
      (libsource (lib "eagle-import") (part "VLMU1610-365-135"))
    )
    (comp (ref "U$65")
      (value "VLMU1610-365-135")
      (footprint "eagle-import:SMD_CERAMIC_MID_POWER")
      (libsource (lib "eagle-import") (part "VLMU1610-365-135"))
    )
    (comp (ref "U$66")
      (value "VLMU1610-365-135")
      (footprint "eagle-import:SMD_CERAMIC_MID_POWER")
      (libsource (lib "eagle-import") (part "VLMU1610-365-135"))
    )
    (comp (ref "U$67")
      (value "VLMU1610-365-135")
      (footprint "eagle-import:SMD_CERAMIC_MID_POWER")
      (libsource (lib "eagle-import") (part "VLMU1610-365-135"))
    )
    (comp (ref "U$68")
      (value "VLMU1610-365-135")
      (footprint "eagle-import:SMD_CERAMIC_MID_POWER")
      (libsource (lib "eagle-import") (part "VLMU1610-365-135"))
    )
    (comp (ref "U$69")
      (value "VLMU1610-365-135")
      (footprint "eagle-import:SMD_CERAMIC_MID_POWER")
      (libsource (lib "eagle-import") (part "VLMU1610-365-135"))
    )
    (comp (ref "U$70")
      (value "VLMU1610-365-135")
      (footprint "eagle-import:SMD_CERAMIC_MID_POWER")
      (libsource (lib "eagle-import") (part "VLMU1610-365-135"))
    )
    (comp (ref "U$71")
      (value "VLMU1610-365-135")
      (footprint "eagle-import:SMD_CERAMIC_MID_POWER")
      (libsource (lib "eagle-import") (part "VLMU1610-365-135"))
    )
    (comp (ref "U$72")
      (value "VLMU1610-365-135")
      (footprint "eagle-import:SMD_CERAMIC_MID_POWER")
      (libsource (lib "eagle-import") (part "VLMU1610-365-135"))
    )
    (comp (ref "U$73")
      (value "VLMU1610-365-135")
      (footprint "eagle-import:SMD_CERAMIC_MID_POWER")
      (libsource (lib "eagle-import") (part "VLMU1610-365-135"))
    )
    (comp (ref "U$74")
      (value "VLMU1610-365-135")
      (footprint "eagle-import:SMD_CERAMIC_MID_POWER")
      (libsource (lib "eagle-import") (part "VLMU1610-365-135"))
    )
    (comp (ref "U$75")
      (value "VLMU1610-365-135")
      (footprint "eagle-import:SMD_CERAMIC_MID_POWER")
      (libsource (lib "eagle-import") (part "VLMU1610-365-135"))
    )
    (comp (ref "U$76")
      (value "VLMU1610-365-135")
      (footprint "eagle-import:SMD_CERAMIC_MID_POWER")
      (libsource (lib "eagle-import") (part "VLMU1610-365-135"))
    )
    (comp (ref "U$77")
      (value "VLMU1610-365-135")
      (footprint "eagle-import:SMD_CERAMIC_MID_POWER")
      (libsource (lib "eagle-import") (part "VLMU1610-365-135"))
    )
    (comp (ref "U$78")
      (value "VLMU1610-365-135")
      (footprint "eagle-import:SMD_CERAMIC_MID_POWER")
      (libsource (lib "eagle-import") (part "VLMU1610-365-135"))
    )
    (comp (ref "U$79")
      (value "VLMU1610-365-135")
      (footprint "eagle-import:SMD_CERAMIC_MID_POWER")
      (libsource (lib "eagle-import") (part "VLMU1610-365-135"))
    )
    (comp (ref "U$80")
      (value "VLMU1610-365-135")
      (footprint "eagle-import:SMD_CERAMIC_MID_POWER")
      (libsource (lib "eagle-import") (part "VLMU1610-365-135"))
    )
    (comp (ref "U$81")
      (value "VLMU1610-365-135")
      (footprint "eagle-import:SMD_CERAMIC_MID_POWER")
      (libsource (lib "eagle-import") (part "VLMU1610-365-135"))
    )
    (comp (ref "U$82")
      (value "VLMU1610-365-135")
      (footprint "eagle-import:SMD_CERAMIC_MID_POWER")
      (libsource (lib "eagle-import") (part "VLMU1610-365-135"))
    )
    (comp (ref "U$83")
      (value "VLMU1610-365-135")
      (footprint "eagle-import:SMD_CERAMIC_MID_POWER")
      (libsource (lib "eagle-import") (part "VLMU1610-365-135"))
    )
    (comp (ref "U$84")
      (value "VLMU1610-365-135")
      (footprint "eagle-import:SMD_CERAMIC_MID_POWER")
      (libsource (lib "eagle-import") (part "VLMU1610-365-135"))
    )
    (comp (ref "U$85")
      (value "VLMU1610-365-135")
      (footprint "eagle-import:SMD_CERAMIC_MID_POWER")
      (libsource (lib "eagle-import") (part "VLMU1610-365-135"))
    )
    (comp (ref "U$86")
      (value "VLMU1610-365-135")
      (footprint "eagle-import:SMD_CERAMIC_MID_POWER")
      (libsource (lib "eagle-import") (part "VLMU1610-365-135"))
    )
    (comp (ref "U$87")
      (value "VLMU1610-365-135")
      (footprint "eagle-import:SMD_CERAMIC_MID_POWER")
      (libsource (lib "eagle-import") (part "VLMU1610-365-135"))
    )
    (comp (ref "U$88")
      (value "VLMU1610-365-135")
      (footprint "eagle-import:SMD_CERAMIC_MID_POWER")
      (libsource (lib "eagle-import") (part "VLMU1610-365-135"))
    )
    (comp (ref "U$89")
      (value "VLMU1610-365-135")
      (footprint "eagle-import:SMD_CERAMIC_MID_POWER")
      (libsource (lib "eagle-import") (part "VLMU1610-365-135"))
    )
    (comp (ref "U$90")
      (value "VLMU1610-365-135")
      (footprint "eagle-import:SMD_CERAMIC_MID_POWER")
      (libsource (lib "eagle-import") (part "VLMU1610-365-135"))
    )
    (comp (ref "U$91")
      (value "VLMU1610-365-135")
      (footprint "eagle-import:SMD_CERAMIC_MID_POWER")
      (libsource (lib "eagle-import") (part "VLMU1610-365-135"))
    )
    (comp (ref "U$92")
      (value "VLMU1610-365-135")
      (footprint "eagle-import:SMD_CERAMIC_MID_POWER")
      (libsource (lib "eagle-import") (part "VLMU1610-365-135"))
    )
    (comp (ref "U$93")
      (value "VLMU1610-365-135")
      (footprint "eagle-import:SMD_CERAMIC_MID_POWER")
      (libsource (lib "eagle-import") (part "VLMU1610-365-135"))
    )
    (comp (ref "U$94")
      (value "VLMU1610-365-135")
      (footprint "eagle-import:SMD_CERAMIC_MID_POWER")
      (libsource (lib "eagle-import") (part "VLMU1610-365-135"))
    )
    (comp (ref "U$95")
      (value "VLMU1610-365-135")
      (footprint "eagle-import:SMD_CERAMIC_MID_POWER")
      (libsource (lib "eagle-import") (part "VLMU1610-365-135"))
    )
    (comp (ref "U$96")
      (value "VLMU1610-365-135")
      (footprint "eagle-import:SMD_CERAMIC_MID_POWER")
      (libsource (lib "eagle-import") (part "VLMU1610-365-135"))
    )
    (comp (ref "C9")
      (value "100n")
      (footprint "eagle-import:C1206K")
      (libsource (lib "eagle-import") (part "C-EUC1206K"))
    )
    (comp (ref "C11")
      (value "100u / 6V3")
      (footprint "eagle-import:C1206K")
      (libsource (lib "eagle-import") (part "C-EUC1206K"))
    )
    (comp (ref "C15")
      (value "100n")
      (footprint "eagle-import:C1206K")
      (libsource (lib "eagle-import") (part "C-EUC1206K"))
    )
    (comp (ref "C16")
      (value "100u / 6V3")
      (footprint "eagle-import:C1206K")
      (libsource (lib "eagle-import") (part "C-EUC1206K"))
    )
    (comp (ref "C17")
      (value "100n")
      (footprint "eagle-import:C1206K")
      (libsource (lib "eagle-import") (part "C-EUC1206K"))
    )
    (comp (ref "C18")
      (value "100u / 6V3")
      (footprint "eagle-import:C1206K")
      (libsource (lib "eagle-import") (part "C-EUC1206K"))
    )
    (comp (ref "C19")
      (value "100n")
      (footprint "eagle-import:C1206K")
      (libsource (lib "eagle-import") (part "C-EUC1206K"))
    )
    (comp (ref "C20")
      (value "100u / 6V3")
      (footprint "eagle-import:C1206K")
      (libsource (lib "eagle-import") (part "C-EUC1206K"))
    )
    (comp (ref "C21")
      (value "100n")
      (footprint "eagle-import:C1206K")
      (libsource (lib "eagle-import") (part "C-EUC1206K"))
    )
    (comp (ref "C22")
      (value "100u / 6V3")
      (footprint "eagle-import:C1206K")
      (libsource (lib "eagle-import") (part "C-EUC1206K"))
    )
    (comp (ref "C23")
      (value "100n")
      (footprint "eagle-import:C1206K")
      (libsource (lib "eagle-import") (part "C-EUC1206K"))
    )
    (comp (ref "C24")
      (value "100u / 6V3")
      (footprint "eagle-import:C1206K")
      (libsource (lib "eagle-import") (part "C-EUC1206K"))
    )
    (comp (ref "C25")
      (value "100n")
      (footprint "eagle-import:C1206K")
      (libsource (lib "eagle-import") (part "C-EUC1206K"))
    )
    (comp (ref "C26")
      (value "100u / 6V3")
      (footprint "eagle-import:C1206K")
      (libsource (lib "eagle-import") (part "C-EUC1206K"))
    )
    (comp (ref "C27")
      (value "100n")
      (footprint "eagle-import:C1206K")
      (libsource (lib "eagle-import") (part "C-EUC1206K"))
    )
    (comp (ref "C28")
      (value "100u / 6V3")
      (footprint "eagle-import:C1206K")
      (libsource (lib "eagle-import") (part "C-EUC1206K"))
    )
    (comp (ref "J1")
      (value "WE_629105136821")
      (footprint "eagle-import:629105136821")
      (libsource (lib "eagle-import") (part "WE_629105136821"))
    )
    (comp (ref "J3")
      (value "WE_629105136821")
      (footprint "eagle-import:629105136821")
      (libsource (lib "eagle-import") (part "WE_629105136821"))
    )
    (comp (ref "J4")
      (value "WE_629105136821")
      (footprint "eagle-import:629105136821")
      (libsource (lib "eagle-import") (part "WE_629105136821"))
    )
    (comp (ref "J5")
      (value "WE_629105136821")
      (footprint "eagle-import:629105136821")
      (libsource (lib "eagle-import") (part "WE_629105136821"))
    )
    (comp (ref "PAD2")
      (value "GND")
      (footprint "eagle-import:2,54_1,0")
      (libsource (lib "eagle-import") (part "2,54/1,0"))
    )
    (comp (ref "PAD3")
      (value "+3V3")
      (footprint "eagle-import:2,54_1,0")
      (libsource (lib "eagle-import") (part "2,54/1,0"))
    )
    (comp (ref "PAD4")
      (value "VCC")
      (footprint "eagle-import:2,54_1,0")
      (libsource (lib "eagle-import") (part "2,54/1,0"))
    )
    (comp (ref "PAD5")
      (value "GND")
      (footprint "eagle-import:2,54_1,0")
      (libsource (lib "eagle-import") (part "2,54/1,0"))
    )
    (comp (ref "PAD6")
      (value "+3V3")
      (footprint "eagle-import:2,54_1,0")
      (libsource (lib "eagle-import") (part "2,54/1,0"))
    )
    (comp (ref "PAD7")
      (value "VCC")
      (footprint "eagle-import:2,54_1,0")
      (libsource (lib "eagle-import") (part "2,54/1,0"))
    )
    (comp (ref "PAD8")
      (value "GND")
      (footprint "eagle-import:2,54_1,0")
      (libsource (lib "eagle-import") (part "2,54/1,0"))
    )
    (comp (ref "PAD9")
      (value "+3V3")
      (footprint "eagle-import:2,54_1,0")
      (libsource (lib "eagle-import") (part "2,54/1,0"))
    )
    (comp (ref "PAD10")
      (value "VCC")
      (footprint "eagle-import:2,54_1,0")
      (libsource (lib "eagle-import") (part "2,54/1,0"))
    )
    (comp (ref "PAD11")
      (value "GND")
      (footprint "eagle-import:2,54_1,0")
      (libsource (lib "eagle-import") (part "2,54/1,0"))
    )
    (comp (ref "PAD12")
      (value "+3V3")
      (footprint "eagle-import:2,54_1,0")
      (libsource (lib "eagle-import") (part "2,54/1,0"))
    )
    (comp (ref "PAD13")
      (value "VCC")
      (footprint "eagle-import:2,54_1,0")
      (libsource (lib "eagle-import") (part "2,54/1,0"))
    )
    (comp (ref "R19")
      (value "0R")
      (footprint "eagle-import:R1206")
      (libsource (lib "eagle-import") (part "R-EU_R1206"))
    )
    (comp (ref "R20")
      (value "0R")
      (footprint "eagle-import:R1206")
      (libsource (lib "eagle-import") (part "R-EU_R1206"))
    )
    (comp (ref "R25")
      (value "0R")
      (footprint "eagle-import:R1206")
      (libsource (lib "eagle-import") (part "R-EU_R1206"))
    )
    (comp (ref "R26")
      (value "0R")
      (footprint "eagle-import:R1206")
      (libsource (lib "eagle-import") (part "R-EU_R1206"))
    )
    (comp (ref "U$99")
      (value "LOGO_RESTRICT")
      (footprint "eagle-import:LOGO_RESTRICT")
      (libsource (lib "eagle-import") (part "LOGO_RESTRICT"))
    )
    (comp (ref "C29")
      (value "10u/16V")
      (footprint "eagle-import:C1206K")
      (libsource (lib "eagle-import") (part "C-EUC1206K"))
    )
    (comp (ref "C30")
      (value "100n")
      (footprint "eagle-import:C1206K")
      (libsource (lib "eagle-import") (part "C-EUC1206K"))
    )
    (comp (ref "DISPLAY")
      (value "FE04-1")
      (footprint "eagle-import:FE04")
      (libsource (lib "eagle-import") (part "FE04-1"))
    )
    (comp (ref "LED1")
      (value "KPT-1608LVSECK-J3-PRV")
      (footprint "eagle-import:MH_KINGBRIGHT_1.6X0.8")
      (libsource (lib "eagle-import") (part "KPT-1608LVSECK-J3-PRV"))
    )
    (comp (ref "LED2")
      (value "KPT-1608LVZGCK")
      (footprint "eagle-import:MH_KINGBRIGHT_1.6X0.8")
      (libsource (lib "eagle-import") (part "KPT-1608LVZGCK"))
    )
    (comp (ref "PAD1")
      (value "2,54/1,0")
      (footprint "eagle-import:2,54_1,0")
      (libsource (lib "eagle-import") (part "2,54/1,0"))
    )
    (comp (ref "PAD16")
      (value "2,54/1,0")
      (footprint "eagle-import:2,54_1,0")
      (libsource (lib "eagle-import") (part "2,54/1,0"))
    )
    (comp (ref "PAD17")
      (value "2,54/1,0")
      (footprint "eagle-import:2,54_1,0")
      (libsource (lib "eagle-import") (part "2,54/1,0"))
    )
    (comp (ref "PAD18")
      (value "2,54/1,0")
      (footprint "eagle-import:2,54_1,0")
      (libsource (lib "eagle-import") (part "2,54/1,0"))
    )
    (comp (ref "PAD19")
      (value "2,54/1,0")
      (footprint "eagle-import:2,54_1,0")
      (libsource (lib "eagle-import") (part "2,54/1,0"))
    )
    (comp (ref "R6")
      (value "1K")
      (footprint "eagle-import:R1206")
      (libsource (lib "eagle-import") (part "R-EU_R1206"))
    )
    (comp (ref "R9")
      (value "10K")
      (footprint "eagle-import:R1206")
      (libsource (lib "eagle-import") (part "R-EU_R1206"))
    )
    (comp (ref "R13")
      (value "10K")
      (footprint "eagle-import:R1206")
      (libsource (lib "eagle-import") (part "R-EU_R1206"))
    )
    (comp (ref "R14")
      (value "0R")
      (footprint "eagle-import:R1206")
      (libsource (lib "eagle-import") (part "R-EU_R1206"))
    )
    (comp (ref "R15")
      (value "0R")
      (footprint "eagle-import:R1206")
      (libsource (lib "eagle-import") (part "R-EU_R1206"))
    )
    (comp (ref "R18")
      (value "1K")
      (footprint "eagle-import:R1206")
      (libsource (lib "eagle-import") (part "R-EU_R1206"))
    )
    (comp (ref "R21")
      (value "750R")
      (footprint "eagle-import:R1206")
      (libsource (lib "eagle-import") (part "R-EU_R1206"))
    )
    (comp (ref "R22")
      (value "330R")
      (footprint "eagle-import:R1206")
      (libsource (lib "eagle-import") (part "R-EU_R1206"))
    )
    (comp (ref "R23")
      (value "10K")
      (footprint "eagle-import:R1206")
      (libsource (lib "eagle-import") (part "R-EU_R1206"))
    )
    (comp (ref "R24")
      (value "0R")
      (footprint "eagle-import:R1206")
      (libsource (lib "eagle-import") (part "R-EU_R1206"))
    )
    (comp (ref "ROTARY_ENCODER")
      (value "FE05-1")
      (footprint "eagle-import:FE05")
      (libsource (lib "eagle-import") (part "FE05-1"))
    )
    (comp (ref "SV_FAN")
      (value "FE02-1")
      (footprint "eagle-import:FE02")
      (libsource (lib "eagle-import") (part "FE02-1"))
    )
    (comp (ref "U$97")
      (value "BLUETOOTH-RN-41\"")
      (footprint "eagle-import:RN41")
      (libsource (lib "eagle-import") (part "BLUETOOTH-RN-41{dblquote}"))
    )
  )
  (nets
    (net (code "1") (name "+3V3") (class "Default")
      (node (ref "C1") (pin "2") (pinfunction "2_2") (pintype "passive"))
      (node (ref "C10") (pin "1") (pinfunction "1_1") (pintype "passive"))
      (node (ref "C11") (pin "1") (pinfunction "1_1") (pintype "passive"))
      (node (ref "C13") (pin "1") (pinfunction "1_1") (pintype "passive"))
      (node (ref "C19") (pin "1") (pinfunction "1_1") (pintype "passive"))
      (node (ref "C2") (pin "2") (pinfunction "2_2") (pintype "passive"))
      (node (ref "C20") (pin "1") (pinfunction "1_1") (pintype "passive"))
      (node (ref "C23") (pin "1") (pinfunction "1_1") (pintype "passive"))
      (node (ref "C24") (pin "1") (pinfunction "1_1") (pintype "passive"))
      (node (ref "C27") (pin "1") (pinfunction "1_1") (pintype "passive"))
      (node (ref "C28") (pin "1") (pinfunction "1_1") (pintype "passive"))
      (node (ref "C29") (pin "1") (pinfunction "1_1") (pintype "passive"))
      (node (ref "C3") (pin "2") (pinfunction "2_2") (pintype "passive"))
      (node (ref "C30") (pin "1") (pinfunction "1_1") (pintype "passive"))
      (node (ref "C31") (pin "1") (pinfunction "1_1") (pintype "passive"))
      (node (ref "C32") (pin "1") (pinfunction "1_1") (pintype "passive"))
      (node (ref "C4") (pin "2") (pinfunction "2_2") (pintype "passive"))
      (node (ref "C5") (pin "2") (pinfunction "2_2") (pintype "passive"))
      (node (ref "C6") (pin "2") (pinfunction "2_2") (pintype "passive"))
      (node (ref "C7") (pin "2") (pinfunction "2_2") (pintype "passive"))
      (node (ref "C8") (pin "2") (pinfunction "2_2") (pintype "passive"))
      (node (ref "C9") (pin "1") (pinfunction "1_1") (pintype "passive"))
      (node (ref "DISPLAY") (pin "4") (pinfunction "4_4") (pintype "passive"))
      (node (ref "FE02") (pin "14") (pinfunction "14_14") (pintype "passive"))
      (node (ref "IC1") (pin "32") (pinfunction "VCC_32") (pintype "power_in"))
      (node (ref "IC2") (pin "32") (pinfunction "VCC_32") (pintype "power_in"))
      (node (ref "IC3") (pin "32") (pinfunction "VCC_32") (pintype "power_in"))
      (node (ref "IC4") (pin "32") (pinfunction "VCC_32") (pintype "power_in"))
      (node (ref "IC5") (pin "8") (pinfunction "VDD_8") (pintype "power_in"))
      (node (ref "IC6") (pin "8") (pinfunction "VDD_8") (pintype "power_in"))
      (node (ref "J1") (pin "3") (pinfunction "D+_3") (pintype "bidirectional"))
      (node (ref "J3") (pin "3") (pinfunction "D+_3") (pintype "bidirectional"))
      (node (ref "J4") (pin "3") (pinfunction "D+_3") (pintype "bidirectional"))
      (node (ref "J5") (pin "3") (pinfunction "D+_3") (pintype "bidirectional"))
      (node (ref "PAD12") (pin "1") (pinfunction "P_1") (pintype "passive"))
      (node (ref "PAD3") (pin "1") (pinfunction "P_1") (pintype "passive"))
      (node (ref "PAD6") (pin "1") (pinfunction "P_1") (pintype "passive"))
      (node (ref "PAD9") (pin "1") (pinfunction "P_1") (pintype "passive"))
      (node (ref "Q2") (pin "E") (pinfunction "E_E") (pintype "passive"))
      (node (ref "R11") (pin "1") (pinfunction "1_1") (pintype "passive"))
      (node (ref "R12") (pin "2") (pinfunction "2_2") (pintype "passive"))
      (node (ref "R17") (pin "1") (pinfunction "1_1") (pintype "passive"))
      (node (ref "R3") (pin "2") (pinfunction "2_2") (pintype "passive"))
      (node (ref "R34") (pin "1") (pinfunction "1_1") (pintype "passive"))
      (node (ref "R36") (pin "1") (pinfunction "1_1") (pintype "passive"))
      (node (ref "R37") (pin "1") (pinfunction "1_1") (pintype "passive"))
      (node (ref "R39") (pin "2") (pinfunction "2_2") (pintype "passive"))
      (node (ref "R9") (pin "2") (pinfunction "2_2") (pintype "passive"))
      (node (ref "ROTARY_ENCODER") (pin "2") (pinfunction "2_2") (pintype "passive"))
      (node (ref "TP1") (pin "TP") (pinfunction "TP_TP") (pintype "input"))
      (node (ref "TP3") (pin "TP") (pinfunction "TP_TP") (pintype "input"))
      (node (ref "TP5") (pin "TP") (pinfunction "TP_TP") (pintype "input"))
      (node (ref "TP7") (pin "TP") (pinfunction "TP_TP") (pintype "input"))
      (node (ref "U$97") (pin "11") (pinfunction "VDD_11") (pintype "bidirectional"))
      (node (ref "U1") (pin "1") (pinfunction "VDD_I/O_1") (pintype "passive"))
      (node (ref "U1") (pin "6") (pinfunction "VS_6") (pintype "passive"))
    )
    (net (code "2") (name "ALERT_1") (class "Default")
      (node (ref "FE02") (pin "10") (pinfunction "10_10") (pintype "passive"))
      (node (ref "IC5") (pin "3") (pinfunction "ALERT_3") (pintype "output"))
      (node (ref "R34") (pin "2") (pinfunction "2_2") (pintype "passive"))
      (node (ref "R38") (pin "2") (pinfunction "2_2") (pintype "passive"))
    )
    (net (code "3") (name "ALERT_2") (class "Default")
      (node (ref "FE02") (pin "11") (pinfunction "11_11") (pintype "passive"))
      (node (ref "IC6") (pin "3") (pinfunction "ALERT_3") (pintype "output"))
      (node (ref "R37") (pin "2") (pinfunction "2_2") (pintype "passive"))
      (node (ref "R38") (pin "1") (pinfunction "1_1") (pintype "passive"))
    )
    (net (code "4") (name "BLANK") (class "Default")
      (node (ref "FE01") (pin "5") (pinfunction "5_5") (pintype "passive"))
      (node (ref "IC1") (pin "2") (pinfunction "BLANK_2") (pintype "input"))
      (node (ref "IC2") (pin "2") (pinfunction "BLANK_2") (pintype "input"))
      (node (ref "IC3") (pin "2") (pinfunction "BLANK_2") (pintype "input"))
      (node (ref "IC4") (pin "2") (pinfunction "BLANK_2") (pintype "input"))
      (node (ref "R17") (pin "2") (pinfunction "2_2") (pintype "passive"))
      (node (ref "R41") (pin "1") (pinfunction "1_1") (pintype "passive"))
    )
    (net (code "5") (name "CLK") (class "Default")
      (node (ref "FE02") (pin "1") (pinfunction "1_1") (pintype "passive"))
      (node (ref "IC1") (pin "3") (pinfunction "SCLK_3") (pintype "input"))
      (node (ref "IC2") (pin "3") (pinfunction "SCLK_3") (pintype "input"))
      (node (ref "IC3") (pin "3") (pinfunction "SCLK_3") (pintype "input"))
      (node (ref "IC4") (pin "3") (pinfunction "SCLK_3") (pintype "input"))
    )
    (net (code "6") (name "CTS") (class "Default")
      (node (ref "FE02") (pin "3") (pinfunction "3_3") (pintype "passive"))
      (node (ref "R18") (pin "1") (pinfunction "1_1") (pintype "passive"))
    )
    (net (code "7") (name "D-_EXT") (class "Default")
      (node (ref "FE01") (pin "2") (pinfunction "2_2") (pintype "passive"))
      (node (ref "J1") (pin "2") (pinfunction "D-_2") (pintype "bidirectional"))
      (node (ref "J3") (pin "2") (pinfunction "D-_2") (pintype "bidirectional"))
      (node (ref "J4") (pin "2") (pinfunction "D-_2") (pintype "bidirectional"))
      (node (ref "J5") (pin "2") (pinfunction "D-_2") (pintype "bidirectional"))
      (node (ref "R16") (pin "1") (pinfunction "1_1") (pintype "passive"))
    )
    (net (code "8") (name "DATA") (class "Default")
      (node (ref "FE01") (pin "13") (pinfunction "13_13") (pintype "passive"))
      (node (ref "IC1") (pin "4") (pinfunction "SIN_4") (pintype "input"))
      (node (ref "IC2") (pin "4") (pinfunction "SIN_4") (pintype "input"))
      (node (ref "IC3") (pin "4") (pinfunction "SIN_4") (pintype "input"))
      (node (ref "IC4") (pin "4") (pinfunction "SIN_4") (pintype "input"))
    )
    (net (code "9") (name "GND") (class "Default")
      (node (ref "C1") (pin "1") (pinfunction "1_1") (pintype "passive"))
      (node (ref "C10") (pin "2") (pinfunction "2_2") (pintype "passive"))
      (node (ref "C11") (pin "2") (pinfunction "2_2") (pintype "passive"))
      (node (ref "C12") (pin "1") (pinfunction "1_1") (pintype "passive"))
      (node (ref "C13") (pin "2") (pinfunction "2_2") (pintype "passive"))
      (node (ref "C14") (pin "1") (pinfunction "1_1") (pintype "passive"))
      (node (ref "C15") (pin "2") (pinfunction "2_2") (pintype "passive"))
      (node (ref "C16") (pin "2") (pinfunction "2_2") (pintype "passive"))
      (node (ref "C17") (pin "2") (pinfunction "2_2") (pintype "passive"))
      (node (ref "C18") (pin "2") (pinfunction "2_2") (pintype "passive"))
      (node (ref "C19") (pin "2") (pinfunction "2_2") (pintype "passive"))
      (node (ref "C2") (pin "1") (pinfunction "1_1") (pintype "passive"))
      (node (ref "C20") (pin "2") (pinfunction "2_2") (pintype "passive"))
      (node (ref "C21") (pin "2") (pinfunction "2_2") (pintype "passive"))
      (node (ref "C22") (pin "2") (pinfunction "2_2") (pintype "passive"))
      (node (ref "C23") (pin "2") (pinfunction "2_2") (pintype "passive"))
      (node (ref "C24") (pin "2") (pinfunction "2_2") (pintype "passive"))
      (node (ref "C25") (pin "2") (pinfunction "2_2") (pintype "passive"))
      (node (ref "C26") (pin "2") (pinfunction "2_2") (pintype "passive"))
      (node (ref "C27") (pin "2") (pinfunction "2_2") (pintype "passive"))
      (node (ref "C28") (pin "2") (pinfunction "2_2") (pintype "passive"))
      (node (ref "C29") (pin "2") (pinfunction "2_2") (pintype "passive"))
      (node (ref "C3") (pin "1") (pinfunction "1_1") (pintype "passive"))
      (node (ref "C30") (pin "2") (pinfunction "2_2") (pintype "passive"))
      (node (ref "C31") (pin "2") (pinfunction "2_2") (pintype "passive"))
      (node (ref "C32") (pin "2") (pinfunction "2_2") (pintype "passive"))
      (node (ref "C4") (pin "1") (pinfunction "1_1") (pintype "passive"))
      (node (ref "C5") (pin "1") (pinfunction "1_1") (pintype "passive"))
      (node (ref "C6") (pin "1") (pinfunction "1_1") (pintype "passive"))
      (node (ref "C7") (pin "1") (pinfunction "1_1") (pintype "passive"))
      (node (ref "C8") (pin "1") (pinfunction "1_1") (pintype "passive"))
      (node (ref "C9") (pin "2") (pinfunction "2_2") (pintype "passive"))
      (node (ref "DISPLAY") (pin "3") (pinfunction "3_3") (pintype "passive"))
      (node (ref "FE01") (pin "1") (pinfunction "1_1") (pintype "passive"))
      (node (ref "IC1") (pin "1") (pinfunction "GND_1") (pintype "power_in"))
      (node (ref "IC1") (pin "EXP") (pinfunction "PAD_EXP") (pintype "passive"))
      (node (ref "IC2") (pin "1") (pinfunction "GND_1") (pintype "power_in"))
      (node (ref "IC2") (pin "EXP") (pinfunction "PAD_EXP") (pintype "passive"))
      (node (ref "IC3") (pin "1") (pinfunction "GND_1") (pintype "power_in"))
      (node (ref "IC3") (pin "EXP") (pinfunction "PAD_EXP") (pintype "passive"))
      (node (ref "IC4") (pin "1") (pinfunction "GND_1") (pintype "power_in"))
      (node (ref "IC4") (pin "EXP") (pinfunction "PAD_EXP") (pintype "passive"))
      (node (ref "IC5") (pin "4") (pinfunction "GND_4") (pintype "power_in"))
      (node (ref "IC6") (pin "4") (pinfunction "GND_4") (pintype "power_in"))
      (node (ref "J1") (pin "5") (pinfunction "GND_5") (pintype "power_in"))
      (node (ref "J3") (pin "5") (pinfunction "GND_5") (pintype "power_in"))
      (node (ref "J4") (pin "5") (pinfunction "GND_5") (pintype "power_in"))
      (node (ref "J5") (pin "5") (pinfunction "GND_5") (pintype "power_in"))
      (node (ref "LED1") (pin "C") (pinfunction "C_C") (pintype "passive"))
      (node (ref "LED2") (pin "C") (pinfunction "C_C") (pintype "passive"))
      (node (ref "LED3") (pin "C") (pinfunction "C_C") (pintype "passive"))
      (node (ref "PAD11") (pin "1") (pinfunction "P_1") (pintype "passive"))
      (node (ref "PAD15") (pin "1") (pinfunction "P_1") (pintype "passive"))
      (node (ref "PAD2") (pin "1") (pinfunction "P_1") (pintype "passive"))
      (node (ref "PAD5") (pin "1") (pinfunction "P_1") (pintype "passive"))
      (node (ref "PAD8") (pin "1") (pinfunction "P_1") (pintype "passive"))
      (node (ref "R10") (pin "2") (pinfunction "2_2") (pintype "passive"))
      (node (ref "R13") (pin "1") (pinfunction "1_1") (pintype "passive"))
      (node (ref "R19") (pin "2") (pinfunction "2_2") (pintype "passive"))
      (node (ref "R2") (pin "2") (pinfunction "S_2") (pintype "passive"))
      (node (ref "R2") (pin "3") (pinfunction "E_3") (pintype "passive"))
      (node (ref "R20") (pin "2") (pinfunction "2_2") (pintype "passive"))
      (node (ref "R23") (pin "2") (pinfunction "2_2") (pintype "passive"))
      (node (ref "R25") (pin "2") (pinfunction "2_2") (pintype "passive"))
      (node (ref "R26") (pin "2") (pinfunction "2_2") (pintype "passive"))
      (node (ref "R35") (pin "2") (pinfunction "2_2") (pintype "passive"))
      (node (ref "R5") (pin "2") (pinfunction "S_2") (pintype "passive"))
      (node (ref "R5") (pin "3") (pinfunction "E_3") (pintype "passive"))
      (node (ref "ROTARY_ENCODER") (pin "1") (pinfunction "1_1") (pintype "passive"))
      (node (ref "SV_FAN") (pin "2") (pinfunction "2_2") (pintype "passive"))
      (node (ref "U$97") (pin "1") (pinfunction "GND_1") (pintype "bidirectional"))
      (node (ref "U$97") (pin "12") (pinfunction "GND1_12") (pintype "bidirectional"))
      (node (ref "U$97") (pin "28") (pinfunction "GND2_28") (pintype "bidirectional"))
      (node (ref "U$97") (pin "29") (pinfunction "GND3_29") (pintype "bidirectional"))
      (node (ref "U1") (pin "12") (pinfunction "SDO/ALT_ADDRESS_12") (pintype "passive"))
      (node (ref "U1") (pin "2") (pinfunction "GND_2_2") (pintype "passive"))
      (node (ref "U1") (pin "4") (pinfunction "GND_3_4") (pintype "passive"))
      (node (ref "U1") (pin "5") (pinfunction "GND_5") (pintype "passive"))
    )
    (net (code "10") (name "ID_EXT") (class "Default")
      (node (ref "FE01") (pin "3") (pinfunction "3_3") (pintype "passive"))
      (node (ref "J1") (pin "4") (pinfunction "ID_4") (pintype "bidirectional"))
      (node (ref "J3") (pin "4") (pinfunction "ID_4") (pintype "bidirectional"))
      (node (ref "J4") (pin "4") (pinfunction "ID_4") (pintype "bidirectional"))
      (node (ref "J5") (pin "4") (pinfunction "ID_4") (pintype "bidirectional"))
      (node (ref "R14") (pin "1") (pinfunction "1_1") (pintype "passive"))
      (node (ref "R15") (pin "1") (pinfunction "1_1") (pintype "passive"))
    )
    (net (code "11") (name "INT1") (class "Default")
      (node (ref "FE02") (pin "8") (pinfunction "8_8") (pintype "passive"))
      (node (ref "U1") (pin "8") (pinfunction "INT1_8") (pintype "passive"))
    )
    (net (code "12") (name "INT2") (class "Default")
      (node (ref "FE02") (pin "9") (pinfunction "9_9") (pintype "passive"))
      (node (ref "U1") (pin "9") (pinfunction "INT2_9") (pintype "passive"))
    )
    (net (code "13") (name "IREF_1") (class "Default")
      (node (ref "IC1") (pin "31") (pinfunction "IREF_31") (pintype "bidirectional"))
      (node (ref "U$98") (pin "2") (pinfunction "B_2") (pintype "passive"))
    )
    (net (code "14") (name "IREF_2") (class "Default")
      (node (ref "IC2") (pin "31") (pinfunction "IREF_31") (pintype "bidirectional"))
      (node (ref "U$98") (pin "1") (pinfunction "A_1") (pintype "passive"))
    )
    (net (code "15") (name "IREF_3") (class "Default")
      (node (ref "IC3") (pin "31") (pinfunction "IREF_31") (pintype "bidirectional"))
      (node (ref "U$100") (pin "2") (pinfunction "B_2") (pintype "passive"))
    )
    (net (code "16") (name "IREF_4") (class "Default")
      (node (ref "IC4") (pin "31") (pinfunction "IREF_31") (pintype "bidirectional"))
      (node (ref "U$100") (pin "1") (pinfunction "A_1") (pintype "passive"))
    )
    (net (code "17") (name "LATCH1") (class "Default")
      (node (ref "FE01") (pin "10") (pinfunction "10_10") (pintype "passive"))
      (node (ref "IC1") (pin "30") (pinfunction "XLAT_30") (pintype "input"))
    )
    (net (code "18") (name "LATCH2") (class "Default")
      (node (ref "FE01") (pin "9") (pinfunction "9_9") (pintype "passive"))
      (node (ref "IC2") (pin "30") (pinfunction "XLAT_30") (pintype "input"))
    )
    (net (code "19") (name "LATCH3") (class "Default")
      (node (ref "FE02") (pin "5") (pinfunction "5_5") (pintype "passive"))
      (node (ref "IC3") (pin "30") (pinfunction "XLAT_30") (pintype "input"))
    )
    (net (code "20") (name "LATCH4") (class "Default")
      (node (ref "FE02") (pin "4") (pinfunction "4_4") (pintype "passive"))
      (node (ref "IC4") (pin "30") (pinfunction "XLAT_30") (pintype "input"))
    )
    (net (code "21") (name "Net-(IC1A-OUT0)") (class "Default")
      (node (ref "IC1") (pin "5") (pinfunction "OUT0_5") (pintype "open_collector"))
      (node (ref "U$1") (pin "P$2") (pinfunction "C_P$2") (pintype "passive"))
    )
    (net (code "22") (name "Net-(IC1A-OUT1)") (class "Default")
      (node (ref "IC1") (pin "6") (pinfunction "OUT1_6") (pintype "open_collector"))
      (node (ref "U$2") (pin "P$2") (pinfunction "C_P$2") (pintype "passive"))
    )
    (net (code "23") (name "Net-(IC1A-OUT2)") (class "Default")
      (node (ref "IC1") (pin "7") (pinfunction "OUT2_7") (pintype "open_collector"))
      (node (ref "U$3") (pin "P$2") (pinfunction "C_P$2") (pintype "passive"))
    )
    (net (code "24") (name "Net-(IC1A-OUT3)") (class "Default")
      (node (ref "IC1") (pin "8") (pinfunction "OUT3_8") (pintype "open_collector"))
      (node (ref "U$4") (pin "P$2") (pinfunction "C_P$2") (pintype "passive"))
    )
    (net (code "25") (name "Net-(IC1A-OUT4)") (class "Default")
      (node (ref "IC1") (pin "9") (pinfunction "OUT4_9") (pintype "open_collector"))
      (node (ref "U$5") (pin "P$2") (pinfunction "C_P$2") (pintype "passive"))
    )
    (net (code "26") (name "Net-(IC1A-OUT5)") (class "Default")
      (node (ref "IC1") (pin "10") (pinfunction "OUT5_10") (pintype "open_collector"))
      (node (ref "U$6") (pin "P$2") (pinfunction "C_P$2") (pintype "passive"))
    )
    (net (code "27") (name "Net-(IC1A-OUT6)") (class "Default")
      (node (ref "IC1") (pin "11") (pinfunction "OUT6_11") (pintype "open_collector"))
      (node (ref "U$7") (pin "P$2") (pinfunction "C_P$2") (pintype "passive"))
    )
    (net (code "28") (name "Net-(IC1A-OUT7)") (class "Default")
      (node (ref "IC1") (pin "12") (pinfunction "OUT7_12") (pintype "open_collector"))
      (node (ref "U$8") (pin "P$2") (pinfunction "C_P$2") (pintype "passive"))
    )
    (net (code "29") (name "Net-(IC1A-OUT8)") (class "Default")
      (node (ref "IC1") (pin "13") (pinfunction "OUT8_13") (pintype "open_collector"))
      (node (ref "U$9") (pin "P$2") (pinfunction "C_P$2") (pintype "passive"))
    )
    (net (code "30") (name "Net-(IC1A-OUT9)") (class "Default")
      (node (ref "IC1") (pin "14") (pinfunction "OUT9_14") (pintype "open_collector"))
      (node (ref "U$10") (pin "P$2") (pinfunction "C_P$2") (pintype "passive"))
    )
    (net (code "31") (name "Net-(IC1A-OUT10)") (class "Default")
      (node (ref "IC1") (pin "15") (pinfunction "OUT10_15") (pintype "open_collector"))
      (node (ref "U$11") (pin "P$2") (pinfunction "C_P$2") (pintype "passive"))
    )
    (net (code "32") (name "Net-(IC1A-OUT11)") (class "Default")
      (node (ref "IC1") (pin "16") (pinfunction "OUT11_16") (pintype "open_collector"))
      (node (ref "U$12") (pin "P$2") (pinfunction "C_P$2") (pintype "passive"))
    )
    (net (code "33") (name "Net-(IC1A-OUT12)") (class "Default")
      (node (ref "IC1") (pin "17") (pinfunction "OUT12_17") (pintype "open_collector"))
      (node (ref "U$13") (pin "P$2") (pinfunction "C_P$2") (pintype "passive"))
    )
    (net (code "34") (name "Net-(IC1A-OUT13)") (class "Default")
      (node (ref "IC1") (pin "18") (pinfunction "OUT13_18") (pintype "open_collector"))
      (node (ref "U$14") (pin "P$2") (pinfunction "C_P$2") (pintype "passive"))
    )
    (net (code "35") (name "Net-(IC1A-OUT14)") (class "Default")
      (node (ref "IC1") (pin "19") (pinfunction "OUT14_19") (pintype "open_collector"))
      (node (ref "U$15") (pin "P$2") (pinfunction "C_P$2") (pintype "passive"))
    )
    (net (code "36") (name "Net-(IC1A-OUT15)") (class "Default")
      (node (ref "IC1") (pin "20") (pinfunction "OUT15_20") (pintype "open_collector"))
      (node (ref "U$16") (pin "P$2") (pinfunction "C_P$2") (pintype "passive"))
    )
    (net (code "37") (name "Net-(IC1A-OUT16)") (class "Default")
      (node (ref "IC1") (pin "21") (pinfunction "OUT16_21") (pintype "open_collector"))
      (node (ref "U$17") (pin "P$2") (pinfunction "C_P$2") (pintype "passive"))
    )
    (net (code "38") (name "Net-(IC1A-OUT17)") (class "Default")
      (node (ref "IC1") (pin "22") (pinfunction "OUT17_22") (pintype "open_collector"))
      (node (ref "U$18") (pin "P$2") (pinfunction "C_P$2") (pintype "passive"))
    )
    (net (code "39") (name "Net-(IC1A-OUT18)") (class "Default")
      (node (ref "IC1") (pin "23") (pinfunction "OUT18_23") (pintype "open_collector"))
      (node (ref "U$19") (pin "P$2") (pinfunction "C_P$2") (pintype "passive"))
    )
    (net (code "40") (name "Net-(IC1A-OUT19)") (class "Default")
      (node (ref "IC1") (pin "24") (pinfunction "OUT19_24") (pintype "open_collector"))
      (node (ref "U$20") (pin "P$2") (pinfunction "C_P$2") (pintype "passive"))
    )
    (net (code "41") (name "Net-(IC1A-OUT20)") (class "Default")
      (node (ref "IC1") (pin "25") (pinfunction "OUT20_25") (pintype "open_collector"))
      (node (ref "U$21") (pin "P$2") (pinfunction "C_P$2") (pintype "passive"))
    )
    (net (code "42") (name "Net-(IC1A-OUT21)") (class "Default")
      (node (ref "IC1") (pin "26") (pinfunction "OUT21_26") (pintype "open_collector"))
      (node (ref "U$22") (pin "P$2") (pinfunction "C_P$2") (pintype "passive"))
    )
    (net (code "43") (name "Net-(IC1A-OUT22)") (class "Default")
      (node (ref "IC1") (pin "27") (pinfunction "OUT22_27") (pintype "open_collector"))
      (node (ref "U$23") (pin "P$2") (pinfunction "C_P$2") (pintype "passive"))
    )
    (net (code "44") (name "Net-(IC1A-OUT23)") (class "Default")
      (node (ref "IC1") (pin "28") (pinfunction "OUT23_28") (pintype "open_collector"))
      (node (ref "U$24") (pin "P$2") (pinfunction "C_P$2") (pintype "passive"))
    )
    (net (code "45") (name "Net-(IC2A-OUT0)") (class "Default")
      (node (ref "IC2") (pin "5") (pinfunction "OUT0_5") (pintype "open_collector"))
      (node (ref "U$25") (pin "P$2") (pinfunction "C_P$2") (pintype "passive"))
    )
    (net (code "46") (name "Net-(IC2A-OUT1)") (class "Default")
      (node (ref "IC2") (pin "6") (pinfunction "OUT1_6") (pintype "open_collector"))
      (node (ref "U$26") (pin "P$2") (pinfunction "C_P$2") (pintype "passive"))
    )
    (net (code "47") (name "Net-(IC2A-OUT2)") (class "Default")
      (node (ref "IC2") (pin "7") (pinfunction "OUT2_7") (pintype "open_collector"))
      (node (ref "U$27") (pin "P$2") (pinfunction "C_P$2") (pintype "passive"))
    )
    (net (code "48") (name "Net-(IC2A-OUT3)") (class "Default")
      (node (ref "IC2") (pin "8") (pinfunction "OUT3_8") (pintype "open_collector"))
      (node (ref "U$28") (pin "P$2") (pinfunction "C_P$2") (pintype "passive"))
    )
    (net (code "49") (name "Net-(IC2A-OUT4)") (class "Default")
      (node (ref "IC2") (pin "9") (pinfunction "OUT4_9") (pintype "open_collector"))
      (node (ref "U$29") (pin "P$2") (pinfunction "C_P$2") (pintype "passive"))
    )
    (net (code "50") (name "Net-(IC2A-OUT5)") (class "Default")
      (node (ref "IC2") (pin "10") (pinfunction "OUT5_10") (pintype "open_collector"))
      (node (ref "U$30") (pin "P$2") (pinfunction "C_P$2") (pintype "passive"))
    )
    (net (code "51") (name "Net-(IC2A-OUT6)") (class "Default")
      (node (ref "IC2") (pin "11") (pinfunction "OUT6_11") (pintype "open_collector"))
      (node (ref "U$31") (pin "P$2") (pinfunction "C_P$2") (pintype "passive"))
    )
    (net (code "52") (name "Net-(IC2A-OUT7)") (class "Default")
      (node (ref "IC2") (pin "12") (pinfunction "OUT7_12") (pintype "open_collector"))
      (node (ref "U$32") (pin "P$2") (pinfunction "C_P$2") (pintype "passive"))
    )
    (net (code "53") (name "Net-(IC2A-OUT8)") (class "Default")
      (node (ref "IC2") (pin "13") (pinfunction "OUT8_13") (pintype "open_collector"))
      (node (ref "U$33") (pin "P$2") (pinfunction "C_P$2") (pintype "passive"))
    )
    (net (code "54") (name "Net-(IC2A-OUT9)") (class "Default")
      (node (ref "IC2") (pin "14") (pinfunction "OUT9_14") (pintype "open_collector"))
      (node (ref "U$34") (pin "P$2") (pinfunction "C_P$2") (pintype "passive"))
    )
    (net (code "55") (name "Net-(IC2A-OUT10)") (class "Default")
      (node (ref "IC2") (pin "15") (pinfunction "OUT10_15") (pintype "open_collector"))
      (node (ref "U$35") (pin "P$2") (pinfunction "C_P$2") (pintype "passive"))
    )
    (net (code "56") (name "Net-(IC2A-OUT11)") (class "Default")
      (node (ref "IC2") (pin "16") (pinfunction "OUT11_16") (pintype "open_collector"))
      (node (ref "U$36") (pin "P$2") (pinfunction "C_P$2") (pintype "passive"))
    )
    (net (code "57") (name "Net-(IC2A-OUT12)") (class "Default")
      (node (ref "IC2") (pin "17") (pinfunction "OUT12_17") (pintype "open_collector"))
      (node (ref "U$37") (pin "P$2") (pinfunction "C_P$2") (pintype "passive"))
    )
    (net (code "58") (name "Net-(IC2A-OUT13)") (class "Default")
      (node (ref "IC2") (pin "18") (pinfunction "OUT13_18") (pintype "open_collector"))
      (node (ref "U$38") (pin "P$2") (pinfunction "C_P$2") (pintype "passive"))
    )
    (net (code "59") (name "Net-(IC2A-OUT14)") (class "Default")
      (node (ref "IC2") (pin "19") (pinfunction "OUT14_19") (pintype "open_collector"))
      (node (ref "U$39") (pin "P$2") (pinfunction "C_P$2") (pintype "passive"))
    )
    (net (code "60") (name "Net-(IC2A-OUT15)") (class "Default")
      (node (ref "IC2") (pin "20") (pinfunction "OUT15_20") (pintype "open_collector"))
      (node (ref "U$40") (pin "P$2") (pinfunction "C_P$2") (pintype "passive"))
    )
    (net (code "61") (name "Net-(IC2A-OUT16)") (class "Default")
      (node (ref "IC2") (pin "21") (pinfunction "OUT16_21") (pintype "open_collector"))
      (node (ref "U$41") (pin "P$2") (pinfunction "C_P$2") (pintype "passive"))
    )
    (net (code "62") (name "Net-(IC2A-OUT17)") (class "Default")
      (node (ref "IC2") (pin "22") (pinfunction "OUT17_22") (pintype "open_collector"))
      (node (ref "U$42") (pin "P$2") (pinfunction "C_P$2") (pintype "passive"))
    )
    (net (code "63") (name "Net-(IC2A-OUT18)") (class "Default")
      (node (ref "IC2") (pin "23") (pinfunction "OUT18_23") (pintype "open_collector"))
      (node (ref "U$43") (pin "P$2") (pinfunction "C_P$2") (pintype "passive"))
    )
    (net (code "64") (name "Net-(IC2A-OUT19)") (class "Default")
      (node (ref "IC2") (pin "24") (pinfunction "OUT19_24") (pintype "open_collector"))
      (node (ref "U$44") (pin "P$2") (pinfunction "C_P$2") (pintype "passive"))
    )
    (net (code "65") (name "Net-(IC2A-OUT20)") (class "Default")
      (node (ref "IC2") (pin "25") (pinfunction "OUT20_25") (pintype "open_collector"))
      (node (ref "U$45") (pin "P$2") (pinfunction "C_P$2") (pintype "passive"))
    )
    (net (code "66") (name "Net-(IC2A-OUT21)") (class "Default")
      (node (ref "IC2") (pin "26") (pinfunction "OUT21_26") (pintype "open_collector"))
      (node (ref "U$46") (pin "P$2") (pinfunction "C_P$2") (pintype "passive"))
    )
    (net (code "67") (name "Net-(IC2A-OUT22)") (class "Default")
      (node (ref "IC2") (pin "27") (pinfunction "OUT22_27") (pintype "open_collector"))
      (node (ref "U$47") (pin "P$2") (pinfunction "C_P$2") (pintype "passive"))
    )
    (net (code "68") (name "Net-(IC2A-OUT23)") (class "Default")
      (node (ref "IC2") (pin "28") (pinfunction "OUT23_28") (pintype "open_collector"))
      (node (ref "U$48") (pin "P$2") (pinfunction "C_P$2") (pintype "passive"))
    )
    (net (code "69") (name "Net-(IC3A-OUT0)") (class "Default")
      (node (ref "IC3") (pin "5") (pinfunction "OUT0_5") (pintype "open_collector"))
      (node (ref "U$49") (pin "P$2") (pinfunction "C_P$2") (pintype "passive"))
    )
    (net (code "70") (name "Net-(IC3A-OUT1)") (class "Default")
      (node (ref "IC3") (pin "6") (pinfunction "OUT1_6") (pintype "open_collector"))
      (node (ref "U$50") (pin "P$2") (pinfunction "C_P$2") (pintype "passive"))
    )
    (net (code "71") (name "Net-(IC3A-OUT2)") (class "Default")
      (node (ref "IC3") (pin "7") (pinfunction "OUT2_7") (pintype "open_collector"))
      (node (ref "U$51") (pin "P$2") (pinfunction "C_P$2") (pintype "passive"))
    )
    (net (code "72") (name "Net-(IC3A-OUT3)") (class "Default")
      (node (ref "IC3") (pin "8") (pinfunction "OUT3_8") (pintype "open_collector"))
      (node (ref "U$52") (pin "P$2") (pinfunction "C_P$2") (pintype "passive"))
    )
    (net (code "73") (name "Net-(IC3A-OUT4)") (class "Default")
      (node (ref "IC3") (pin "9") (pinfunction "OUT4_9") (pintype "open_collector"))
      (node (ref "U$53") (pin "P$2") (pinfunction "C_P$2") (pintype "passive"))
    )
    (net (code "74") (name "Net-(IC3A-OUT5)") (class "Default")
      (node (ref "IC3") (pin "10") (pinfunction "OUT5_10") (pintype "open_collector"))
      (node (ref "U$54") (pin "P$2") (pinfunction "C_P$2") (pintype "passive"))
    )
    (net (code "75") (name "Net-(IC3A-OUT6)") (class "Default")
      (node (ref "IC3") (pin "11") (pinfunction "OUT6_11") (pintype "open_collector"))
      (node (ref "U$55") (pin "P$2") (pinfunction "C_P$2") (pintype "passive"))
    )
    (net (code "76") (name "Net-(IC3A-OUT7)") (class "Default")
      (node (ref "IC3") (pin "12") (pinfunction "OUT7_12") (pintype "open_collector"))
      (node (ref "U$56") (pin "P$2") (pinfunction "C_P$2") (pintype "passive"))
    )
    (net (code "77") (name "Net-(IC3A-OUT8)") (class "Default")
      (node (ref "IC3") (pin "13") (pinfunction "OUT8_13") (pintype "open_collector"))
      (node (ref "U$57") (pin "P$2") (pinfunction "C_P$2") (pintype "passive"))
    )
    (net (code "78") (name "Net-(IC3A-OUT9)") (class "Default")
      (node (ref "IC3") (pin "14") (pinfunction "OUT9_14") (pintype "open_collector"))
      (node (ref "U$58") (pin "P$2") (pinfunction "C_P$2") (pintype "passive"))
    )
    (net (code "79") (name "Net-(IC3A-OUT10)") (class "Default")
      (node (ref "IC3") (pin "15") (pinfunction "OUT10_15") (pintype "open_collector"))
      (node (ref "U$59") (pin "P$2") (pinfunction "C_P$2") (pintype "passive"))
    )
    (net (code "80") (name "Net-(IC3A-OUT11)") (class "Default")
      (node (ref "IC3") (pin "16") (pinfunction "OUT11_16") (pintype "open_collector"))
      (node (ref "U$60") (pin "P$2") (pinfunction "C_P$2") (pintype "passive"))
    )
    (net (code "81") (name "Net-(IC3A-OUT12)") (class "Default")
      (node (ref "IC3") (pin "17") (pinfunction "OUT12_17") (pintype "open_collector"))
      (node (ref "U$61") (pin "P$2") (pinfunction "C_P$2") (pintype "passive"))
    )
    (net (code "82") (name "Net-(IC3A-OUT13)") (class "Default")
      (node (ref "IC3") (pin "18") (pinfunction "OUT13_18") (pintype "open_collector"))
      (node (ref "U$62") (pin "P$2") (pinfunction "C_P$2") (pintype "passive"))
    )
    (net (code "83") (name "Net-(IC3A-OUT14)") (class "Default")
      (node (ref "IC3") (pin "19") (pinfunction "OUT14_19") (pintype "open_collector"))
      (node (ref "U$63") (pin "P$2") (pinfunction "C_P$2") (pintype "passive"))
    )
    (net (code "84") (name "Net-(IC3A-OUT15)") (class "Default")
      (node (ref "IC3") (pin "20") (pinfunction "OUT15_20") (pintype "open_collector"))
      (node (ref "U$64") (pin "P$2") (pinfunction "C_P$2") (pintype "passive"))
    )
    (net (code "85") (name "Net-(IC3A-OUT16)") (class "Default")
      (node (ref "IC3") (pin "21") (pinfunction "OUT16_21") (pintype "open_collector"))
      (node (ref "U$65") (pin "P$2") (pinfunction "C_P$2") (pintype "passive"))
    )
    (net (code "86") (name "Net-(IC3A-OUT17)") (class "Default")
      (node (ref "IC3") (pin "22") (pinfunction "OUT17_22") (pintype "open_collector"))
      (node (ref "U$66") (pin "P$2") (pinfunction "C_P$2") (pintype "passive"))
    )
    (net (code "87") (name "Net-(IC3A-OUT18)") (class "Default")
      (node (ref "IC3") (pin "23") (pinfunction "OUT18_23") (pintype "open_collector"))
      (node (ref "U$67") (pin "P$2") (pinfunction "C_P$2") (pintype "passive"))
    )
    (net (code "88") (name "Net-(IC3A-OUT19)") (class "Default")
      (node (ref "IC3") (pin "24") (pinfunction "OUT19_24") (pintype "open_collector"))
      (node (ref "U$68") (pin "P$2") (pinfunction "C_P$2") (pintype "passive"))
    )
    (net (code "89") (name "Net-(IC3A-OUT20)") (class "Default")
      (node (ref "IC3") (pin "25") (pinfunction "OUT20_25") (pintype "open_collector"))
      (node (ref "U$69") (pin "P$2") (pinfunction "C_P$2") (pintype "passive"))
    )
    (net (code "90") (name "Net-(IC3A-OUT21)") (class "Default")
      (node (ref "IC3") (pin "26") (pinfunction "OUT21_26") (pintype "open_collector"))
      (node (ref "U$70") (pin "P$2") (pinfunction "C_P$2") (pintype "passive"))
    )
    (net (code "91") (name "Net-(IC3A-OUT22)") (class "Default")
      (node (ref "IC3") (pin "27") (pinfunction "OUT22_27") (pintype "open_collector"))
      (node (ref "U$71") (pin "P$2") (pinfunction "C_P$2") (pintype "passive"))
    )
    (net (code "92") (name "Net-(IC3A-OUT23)") (class "Default")
      (node (ref "IC3") (pin "28") (pinfunction "OUT23_28") (pintype "open_collector"))
      (node (ref "U$72") (pin "P$2") (pinfunction "C_P$2") (pintype "passive"))
    )
    (net (code "93") (name "Net-(IC4A-OUT0)") (class "Default")
      (node (ref "IC4") (pin "5") (pinfunction "OUT0_5") (pintype "open_collector"))
      (node (ref "U$73") (pin "P$2") (pinfunction "C_P$2") (pintype "passive"))
    )
    (net (code "94") (name "Net-(IC4A-OUT1)") (class "Default")
      (node (ref "IC4") (pin "6") (pinfunction "OUT1_6") (pintype "open_collector"))
      (node (ref "U$74") (pin "P$2") (pinfunction "C_P$2") (pintype "passive"))
    )
    (net (code "95") (name "Net-(IC4A-OUT2)") (class "Default")
      (node (ref "IC4") (pin "7") (pinfunction "OUT2_7") (pintype "open_collector"))
      (node (ref "U$75") (pin "P$2") (pinfunction "C_P$2") (pintype "passive"))
    )
    (net (code "96") (name "Net-(IC4A-OUT3)") (class "Default")
      (node (ref "IC4") (pin "8") (pinfunction "OUT3_8") (pintype "open_collector"))
      (node (ref "U$76") (pin "P$2") (pinfunction "C_P$2") (pintype "passive"))
    )
    (net (code "97") (name "Net-(IC4A-OUT4)") (class "Default")
      (node (ref "IC4") (pin "9") (pinfunction "OUT4_9") (pintype "open_collector"))
      (node (ref "U$77") (pin "P$2") (pinfunction "C_P$2") (pintype "passive"))
    )
    (net (code "98") (name "Net-(IC4A-OUT5)") (class "Default")
      (node (ref "IC4") (pin "10") (pinfunction "OUT5_10") (pintype "open_collector"))
      (node (ref "U$78") (pin "P$2") (pinfunction "C_P$2") (pintype "passive"))
    )
    (net (code "99") (name "Net-(IC4A-OUT6)") (class "Default")
      (node (ref "IC4") (pin "11") (pinfunction "OUT6_11") (pintype "open_collector"))
      (node (ref "U$79") (pin "P$2") (pinfunction "C_P$2") (pintype "passive"))
    )
    (net (code "100") (name "Net-(IC4A-OUT7)") (class "Default")
      (node (ref "IC4") (pin "12") (pinfunction "OUT7_12") (pintype "open_collector"))
      (node (ref "U$80") (pin "P$2") (pinfunction "C_P$2") (pintype "passive"))
    )
    (net (code "101") (name "Net-(IC4A-OUT8)") (class "Default")
      (node (ref "IC4") (pin "13") (pinfunction "OUT8_13") (pintype "open_collector"))
      (node (ref "U$81") (pin "P$2") (pinfunction "C_P$2") (pintype "passive"))
    )
    (net (code "102") (name "Net-(IC4A-OUT9)") (class "Default")
      (node (ref "IC4") (pin "14") (pinfunction "OUT9_14") (pintype "open_collector"))
      (node (ref "U$82") (pin "P$2") (pinfunction "C_P$2") (pintype "passive"))
    )
    (net (code "103") (name "Net-(IC4A-OUT10)") (class "Default")
      (node (ref "IC4") (pin "15") (pinfunction "OUT10_15") (pintype "open_collector"))
      (node (ref "U$83") (pin "P$2") (pinfunction "C_P$2") (pintype "passive"))
    )
    (net (code "104") (name "Net-(IC4A-OUT11)") (class "Default")
      (node (ref "IC4") (pin "16") (pinfunction "OUT11_16") (pintype "open_collector"))
      (node (ref "U$84") (pin "P$2") (pinfunction "C_P$2") (pintype "passive"))
    )
    (net (code "105") (name "Net-(IC4A-OUT12)") (class "Default")
      (node (ref "IC4") (pin "17") (pinfunction "OUT12_17") (pintype "open_collector"))
      (node (ref "U$85") (pin "P$2") (pinfunction "C_P$2") (pintype "passive"))
    )
    (net (code "106") (name "Net-(IC4A-OUT13)") (class "Default")
      (node (ref "IC4") (pin "18") (pinfunction "OUT13_18") (pintype "open_collector"))
      (node (ref "U$86") (pin "P$2") (pinfunction "C_P$2") (pintype "passive"))
    )
    (net (code "107") (name "Net-(IC4A-OUT14)") (class "Default")
      (node (ref "IC4") (pin "19") (pinfunction "OUT14_19") (pintype "open_collector"))
      (node (ref "U$87") (pin "P$2") (pinfunction "C_P$2") (pintype "passive"))
    )
    (net (code "108") (name "Net-(IC4A-OUT15)") (class "Default")
      (node (ref "IC4") (pin "20") (pinfunction "OUT15_20") (pintype "open_collector"))
      (node (ref "U$88") (pin "P$2") (pinfunction "C_P$2") (pintype "passive"))
    )
    (net (code "109") (name "Net-(IC4A-OUT16)") (class "Default")
      (node (ref "IC4") (pin "21") (pinfunction "OUT16_21") (pintype "open_collector"))
      (node (ref "U$89") (pin "P$2") (pinfunction "C_P$2") (pintype "passive"))
    )
    (net (code "110") (name "Net-(IC4A-OUT17)") (class "Default")
      (node (ref "IC4") (pin "22") (pinfunction "OUT17_22") (pintype "open_collector"))
      (node (ref "U$90") (pin "P$2") (pinfunction "C_P$2") (pintype "passive"))
    )
    (net (code "111") (name "Net-(IC4A-OUT18)") (class "Default")
      (node (ref "IC4") (pin "23") (pinfunction "OUT18_23") (pintype "open_collector"))
      (node (ref "U$91") (pin "P$2") (pinfunction "C_P$2") (pintype "passive"))
    )
    (net (code "112") (name "Net-(IC4A-OUT19)") (class "Default")
      (node (ref "IC4") (pin "24") (pinfunction "OUT19_24") (pintype "open_collector"))
      (node (ref "U$92") (pin "P$2") (pinfunction "C_P$2") (pintype "passive"))
    )
    (net (code "113") (name "Net-(IC4A-OUT20)") (class "Default")
      (node (ref "IC4") (pin "25") (pinfunction "OUT20_25") (pintype "open_collector"))
      (node (ref "U$93") (pin "P$2") (pinfunction "C_P$2") (pintype "passive"))
    )
    (net (code "114") (name "Net-(IC4A-OUT21)") (class "Default")
      (node (ref "IC4") (pin "26") (pinfunction "OUT21_26") (pintype "open_collector"))
      (node (ref "U$94") (pin "P$2") (pinfunction "C_P$2") (pintype "passive"))
    )
    (net (code "115") (name "Net-(IC4A-OUT22)") (class "Default")
      (node (ref "IC4") (pin "27") (pinfunction "OUT22_27") (pintype "open_collector"))
      (node (ref "U$95") (pin "P$2") (pinfunction "C_P$2") (pintype "passive"))
    )
    (net (code "116") (name "Net-(IC4A-OUT23)") (class "Default")
      (node (ref "IC4") (pin "28") (pinfunction "OUT23_28") (pintype "open_collector"))
      (node (ref "U$96") (pin "P$2") (pinfunction "C_P$2") (pintype "passive"))
    )
    (net (code "117") (name "Net-(IC5-A0)") (class "Default")
      (node (ref "IC5") (pin "7") (pinfunction "A0_7") (pintype "passive"))
      (node (ref "R11") (pin "2") (pinfunction "2_2") (pintype "passive"))
    )
    (net (code "118") (name "Net-(IC5-A1)") (class "Default")
      (node (ref "IC5") (pin "5") (pinfunction "A2_5") (pintype "passive"))
      (node (ref "IC5") (pin "6") (pinfunction "A1_6") (pintype "passive"))
      (node (ref "R10") (pin "1") (pinfunction "1_1") (pintype "passive"))
    )
    (net (code "119") (name "Net-(IC6-A0)") (class "Default")
      (node (ref "IC6") (pin "5") (pinfunction "A2_5") (pintype "passive"))
      (node (ref "IC6") (pin "7") (pinfunction "A0_7") (pintype "passive"))
      (node (ref "R35") (pin "1") (pinfunction "1_1") (pintype "passive"))
    )
    (net (code "120") (name "Net-(IC6-A1)") (class "Default")
      (node (ref "IC6") (pin "6") (pinfunction "A1_6") (pintype "passive"))
      (node (ref "R36") (pin "2") (pinfunction "2_2") (pintype "passive"))
    )
    (net (code "121") (name "Net-(J1-SHIELD-Pad6)") (class "Default")
      (node (ref "J1") (pin "6") (pinfunction "SHIELD_6") (pintype "power_in"))
      (node (ref "J1") (pin "7") (pinfunction "SHIELD_7") (pintype "power_in"))
      (node (ref "J1") (pin "8") (pinfunction "SHIELD_8") (pintype "power_in"))
      (node (ref "J1") (pin "9") (pinfunction "SHIELD_9") (pintype "power_in"))
      (node (ref "R19") (pin "1") (pinfunction "1_1") (pintype "passive"))
    )
    (net (code "122") (name "Net-(J3-SHIELD-Pad6)") (class "Default")
      (node (ref "J3") (pin "6") (pinfunction "SHIELD_6") (pintype "power_in"))
      (node (ref "J3") (pin "7") (pinfunction "SHIELD_7") (pintype "power_in"))
      (node (ref "J3") (pin "8") (pinfunction "SHIELD_8") (pintype "power_in"))
      (node (ref "J3") (pin "9") (pinfunction "SHIELD_9") (pintype "power_in"))
      (node (ref "R20") (pin "1") (pinfunction "1_1") (pintype "passive"))
    )
    (net (code "123") (name "Net-(J4-SHIELD-Pad6)") (class "Default")
      (node (ref "J4") (pin "6") (pinfunction "SHIELD_6") (pintype "power_in"))
      (node (ref "J4") (pin "7") (pinfunction "SHIELD_7") (pintype "power_in"))
      (node (ref "J4") (pin "8") (pinfunction "SHIELD_8") (pintype "power_in"))
      (node (ref "J4") (pin "9") (pinfunction "SHIELD_9") (pintype "power_in"))
      (node (ref "R25") (pin "1") (pinfunction "1_1") (pintype "passive"))
    )
    (net (code "124") (name "Net-(J5-SHIELD-Pad6)") (class "Default")
      (node (ref "J5") (pin "6") (pinfunction "SHIELD_6") (pintype "power_in"))
      (node (ref "J5") (pin "7") (pinfunction "SHIELD_7") (pintype "power_in"))
      (node (ref "J5") (pin "8") (pinfunction "SHIELD_8") (pintype "power_in"))
      (node (ref "J5") (pin "9") (pinfunction "SHIELD_9") (pintype "power_in"))
      (node (ref "R26") (pin "1") (pinfunction "1_1") (pintype "passive"))
    )
    (net (code "125") (name "Net-(LED1-PadA)") (class "Default")
      (node (ref "LED1") (pin "A") (pinfunction "A_A") (pintype "passive"))
      (node (ref "R21") (pin "2") (pinfunction "2_2") (pintype "passive"))
    )
    (net (code "126") (name "Net-(LED2-PadA)") (class "Default")
      (node (ref "LED2") (pin "A") (pinfunction "A_A") (pintype "passive"))
      (node (ref "R22") (pin "2") (pinfunction "2_2") (pintype "passive"))
    )
    (net (code "127") (name "Net-(PAD1-P)") (class "Default")
      (node (ref "PAD1") (pin "1") (pinfunction "P_1") (pintype "passive"))
      (node (ref "R23") (pin "1") (pinfunction "1_1") (pintype "passive"))
      (node (ref "U$97") (pin "22") (pinfunction "PIO4_22") (pintype "bidirectional"))
    )
    (net (code "128") (name "Net-(PAD14-P)") (class "Default")
      (node (ref "LED3") (pin "A") (pinfunction "A_A") (pintype "passive"))
      (node (ref "PAD14") (pin "1") (pinfunction "P_1") (pintype "passive"))
      (node (ref "R40") (pin "1") (pinfunction "1_1") (pintype "passive"))
    )
    (net (code "129") (name "Net-(PAD16-P)") (class "Default")
      (node (ref "PAD16") (pin "1") (pinfunction "P_1") (pintype "passive"))
      (node (ref "U$97") (pin "2") (pinfunction "SPIMOSI_2") (pintype "bidirectional"))
    )
    (net (code "130") (name "Net-(PAD17-P)") (class "Default")
      (node (ref "PAD17") (pin "1") (pinfunction "P_1") (pintype "passive"))
      (node (ref "U$97") (pin "24") (pinfunction "SPIMISO_24") (pintype "bidirectional"))
    )
    (net (code "131") (name "Net-(PAD18-P)") (class "Default")
      (node (ref "PAD18") (pin "1") (pinfunction "P_1") (pintype "passive"))
      (node (ref "U$97") (pin "23") (pinfunction "SPICSB_23") (pintype "bidirectional"))
    )
    (net (code "132") (name "Net-(PAD19-P)") (class "Default")
      (node (ref "PAD19") (pin "1") (pinfunction "P_1") (pintype "passive"))
      (node (ref "U$97") (pin "6") (pinfunction "SPICLK_6") (pintype "bidirectional"))
    )
    (net (code "133") (name "Net-(Q2-PadB)") (class "Default")
      (node (ref "Q2") (pin "B") (pinfunction "B_B") (pintype "passive"))
      (node (ref "R41") (pin "2") (pinfunction "2_2") (pintype "passive"))
    )
    (net (code "134") (name "Net-(Q2-PadC)") (class "Default")
      (node (ref "Q2") (pin "C") (pinfunction "C_C") (pintype "passive"))
      (node (ref "R16") (pin "2") (pinfunction "2_2") (pintype "passive"))
      (node (ref "R40") (pin "2") (pinfunction "2_2") (pintype "passive"))
    )
    (net (code "135") (name "Net-(R2-A)") (class "Default")
      (node (ref "R1") (pin "1") (pinfunction "1_1") (pintype "passive"))
      (node (ref "R2") (pin "1") (pinfunction "A_1") (pintype "passive"))
    )
    (net (code "136") (name "Net-(R5-A)") (class "Default")
      (node (ref "R4") (pin "1") (pinfunction "1_1") (pintype "passive"))
      (node (ref "R5") (pin "1") (pinfunction "A_1") (pintype "passive"))
    )
    (net (code "137") (name "Net-(U$97-PIO2)") (class "Default")
      (node (ref "R14") (pin "2") (pinfunction "2_2") (pintype "passive"))
      (node (ref "R21") (pin "1") (pinfunction "1_1") (pintype "passive"))
      (node (ref "U$97") (pin "19") (pinfunction "PIO2_19") (pintype "bidirectional"))
    )
    (net (code "138") (name "Net-(U$97-PIO5)") (class "Default")
      (node (ref "R15") (pin "2") (pinfunction "2_2") (pintype "passive"))
      (node (ref "R22") (pin "1") (pinfunction "1_1") (pintype "passive"))
      (node (ref "U$97") (pin "21") (pinfunction "PIO5_21") (pintype "bidirectional"))
    )
    (net (code "139") (name "Net-(U$97-PIO6)") (class "Default")
      (node (ref "R13") (pin "2") (pinfunction "2_2") (pintype "passive"))
      (node (ref "U$97") (pin "3") (pinfunction "PIO6_3") (pintype "bidirectional"))
    )
    (net (code "140") (name "Net-(U$97-PIO7)") (class "Default")
      (node (ref "R9") (pin "1") (pinfunction "1_1") (pintype "passive"))
      (node (ref "U$97") (pin "4") (pinfunction "PIO7_4") (pintype "bidirectional"))
    )
    (net (code "141") (name "Net-(U$97-UARTCTS)") (class "Default")
      (node (ref "R18") (pin "2") (pinfunction "2_2") (pintype "passive"))
      (node (ref "R24") (pin "1") (pinfunction "1_1") (pintype "passive"))
      (node (ref "U$97") (pin "16") (pinfunction "UARTCTS_16") (pintype "bidirectional"))
    )
    (net (code "142") (name "Net-(U$97-UARTRX)") (class "Default")
      (node (ref "R6") (pin "2") (pinfunction "2_2") (pintype "passive"))
      (node (ref "U$97") (pin "13") (pinfunction "UARTRX_13") (pintype "bidirectional"))
    )
    (net (code "143") (name "Net-(U$98-C)") (class "Default")
      (node (ref "R42") (pin "2") (pinfunction "2_2") (pintype "passive"))
      (node (ref "U$98") (pin "3") (pinfunction "C_3") (pintype "passive"))
    )
    (net (code "144") (name "Net-(U$100-C)") (class "Default")
      (node (ref "R7") (pin "2") (pinfunction "2_2") (pintype "passive"))
      (node (ref "R8") (pin "2") (pinfunction "2_2") (pintype "passive"))
      (node (ref "U$100") (pin "3") (pinfunction "C_3") (pintype "passive"))
    )
    (net (code "145") (name "Net-(U$101-A)") (class "Default")
      (node (ref "R7") (pin "1") (pinfunction "1_1") (pintype "passive"))
      (node (ref "U$101") (pin "1") (pinfunction "A_1") (pintype "passive"))
    )
    (net (code "146") (name "Net-(U$101-B)") (class "Default")
      (node (ref "R42") (pin "1") (pinfunction "1_1") (pintype "passive"))
      (node (ref "U$101") (pin "2") (pinfunction "B_2") (pintype "passive"))
    )
    (net (code "147") (name "Net-(U$101-C)") (class "Default")
      (node (ref "R1") (pin "2") (pinfunction "2_2") (pintype "passive"))
      (node (ref "TP9") (pin "TP") (pinfunction "TP_TP") (pintype "input"))
      (node (ref "U$101") (pin "3") (pinfunction "C_3") (pintype "passive"))
    )
    (net (code "148") (name "Net-(U$102-B)") (class "Default")
      (node (ref "R8") (pin "1") (pinfunction "1_1") (pintype "passive"))
      (node (ref "U$102") (pin "2") (pinfunction "B_2") (pintype "passive"))
    )
    (net (code "149") (name "Net-(U$102-C)") (class "Default")
      (node (ref "R4") (pin "2") (pinfunction "2_2") (pintype "passive"))
      (node (ref "TP10") (pin "TP") (pinfunction "TP_TP") (pintype "input"))
      (node (ref "U$102") (pin "3") (pinfunction "C_3") (pintype "passive"))
    )
    (net (code "150") (name "Net-(U1-*CS)") (class "Default")
      (node (ref "R3") (pin "1") (pinfunction "1_1") (pintype "passive"))
      (node (ref "U1") (pin "7") (pinfunction "*CS_7") (pintype "passive"))
    )
    (net (code "151") (name "RE_CLK") (class "Default")
      (node (ref "C14") (pin "2") (pinfunction "2_2") (pintype "passive"))
      (node (ref "FE01") (pin "6") (pinfunction "6_6") (pintype "passive"))
      (node (ref "ROTARY_ENCODER") (pin "5") (pinfunction "5_5") (pintype "passive"))
    )
    (net (code "152") (name "RE_DT") (class "Default")
      (node (ref "C12") (pin "2") (pinfunction "2_2") (pintype "passive"))
      (node (ref "FE01") (pin "7") (pinfunction "7_7") (pintype "passive"))
      (node (ref "ROTARY_ENCODER") (pin "4") (pinfunction "4_4") (pintype "passive"))
    )
    (net (code "153") (name "RE_SW") (class "Default")
      (node (ref "FE01") (pin "8") (pinfunction "8_8") (pintype "passive"))
      (node (ref "ROTARY_ENCODER") (pin "3") (pinfunction "3_3") (pintype "passive"))
    )
    (net (code "154") (name "RTS") (class "Default")
      (node (ref "FE02") (pin "2") (pinfunction "2_2") (pintype "passive"))
      (node (ref "R24") (pin "2") (pinfunction "2_2") (pintype "passive"))
      (node (ref "U$97") (pin "15") (pinfunction "UARTRTS_15") (pintype "bidirectional"))
    )
    (net (code "155") (name "RXD") (class "Default")
      (node (ref "FE01") (pin "12") (pinfunction "12_12") (pintype "passive"))
      (node (ref "R6") (pin "1") (pinfunction "1_1") (pintype "passive"))
    )
    (net (code "156") (name "SCL") (class "Default")
      (node (ref "DISPLAY") (pin "2") (pinfunction "2_2") (pintype "passive"))
      (node (ref "FE02") (pin "7") (pinfunction "7_7") (pintype "passive"))
      (node (ref "IC5") (pin "2") (pinfunction "SCL_2") (pintype "bidirectional"))
      (node (ref "IC6") (pin "2") (pinfunction "SCL_2") (pintype "bidirectional"))
      (node (ref "R12") (pin "1") (pinfunction "1_1") (pintype "passive"))
      (node (ref "U1") (pin "14") (pinfunction "SCL/SCLK_14") (pintype "passive"))
    )
    (net (code "157") (name "SDA") (class "Default")
      (node (ref "DISPLAY") (pin "1") (pinfunction "1_1") (pintype "passive"))
      (node (ref "FE02") (pin "6") (pinfunction "6_6") (pintype "passive"))
      (node (ref "IC5") (pin "1") (pinfunction "SDA_1") (pintype "bidirectional"))
      (node (ref "IC6") (pin "1") (pinfunction "SDA_1") (pintype "bidirectional"))
      (node (ref "R39") (pin "1") (pinfunction "1_1") (pintype "passive"))
      (node (ref "U1") (pin "13") (pinfunction "SDA/SDI/SDIO_13") (pintype "passive"))
    )
    (net (code "158") (name "TXD") (class "Default")
      (node (ref "FE01") (pin "11") (pinfunction "11_11") (pintype "passive"))
      (node (ref "U$97") (pin "14") (pinfunction "UARTTX_14") (pintype "bidirectional"))
    )
    (net (code "159") (name "VCC") (class "Default")
      (node (ref "C15") (pin "1") (pinfunction "1_1") (pintype "passive"))
      (node (ref "C16") (pin "1") (pinfunction "1_1") (pintype "passive"))
      (node (ref "C17") (pin "1") (pinfunction "1_1") (pintype "passive"))
      (node (ref "C18") (pin "1") (pinfunction "1_1") (pintype "passive"))
      (node (ref "C21") (pin "1") (pinfunction "1_1") (pintype "passive"))
      (node (ref "C22") (pin "1") (pinfunction "1_1") (pintype "passive"))
      (node (ref "C25") (pin "1") (pinfunction "1_1") (pintype "passive"))
      (node (ref "C26") (pin "1") (pinfunction "1_1") (pintype "passive"))
      (node (ref "J1") (pin "1") (pinfunction "VBUS_1") (pintype "power_in"))
      (node (ref "J3") (pin "1") (pinfunction "VBUS_1") (pintype "power_in"))
      (node (ref "J4") (pin "1") (pinfunction "VBUS_1") (pintype "power_in"))
      (node (ref "J5") (pin "1") (pinfunction "VBUS_1") (pintype "power_in"))
      (node (ref "PAD10") (pin "1") (pinfunction "P_1") (pintype "passive"))
      (node (ref "PAD13") (pin "1") (pinfunction "P_1") (pintype "passive"))
      (node (ref "PAD4") (pin "1") (pinfunction "P_1") (pintype "passive"))
      (node (ref "PAD7") (pin "1") (pinfunction "P_1") (pintype "passive"))
      (node (ref "SV_FAN") (pin "1") (pinfunction "1_1") (pintype "passive"))
      (node (ref "U$1") (pin "P$1") (pinfunction "A_P$1") (pintype "passive"))
      (node (ref "U$10") (pin "P$1") (pinfunction "A_P$1") (pintype "passive"))
      (node (ref "U$11") (pin "P$1") (pinfunction "A_P$1") (pintype "passive"))
      (node (ref "U$12") (pin "P$1") (pinfunction "A_P$1") (pintype "passive"))
      (node (ref "U$13") (pin "P$1") (pinfunction "A_P$1") (pintype "passive"))
      (node (ref "U$14") (pin "P$1") (pinfunction "A_P$1") (pintype "passive"))
      (node (ref "U$15") (pin "P$1") (pinfunction "A_P$1") (pintype "passive"))
      (node (ref "U$16") (pin "P$1") (pinfunction "A_P$1") (pintype "passive"))
      (node (ref "U$17") (pin "P$1") (pinfunction "A_P$1") (pintype "passive"))
      (node (ref "U$18") (pin "P$1") (pinfunction "A_P$1") (pintype "passive"))
      (node (ref "U$19") (pin "P$1") (pinfunction "A_P$1") (pintype "passive"))
      (node (ref "U$2") (pin "P$1") (pinfunction "A_P$1") (pintype "passive"))
      (node (ref "U$20") (pin "P$1") (pinfunction "A_P$1") (pintype "passive"))
      (node (ref "U$21") (pin "P$1") (pinfunction "A_P$1") (pintype "passive"))
      (node (ref "U$22") (pin "P$1") (pinfunction "A_P$1") (pintype "passive"))
      (node (ref "U$23") (pin "P$1") (pinfunction "A_P$1") (pintype "passive"))
      (node (ref "U$24") (pin "P$1") (pinfunction "A_P$1") (pintype "passive"))
      (node (ref "U$25") (pin "P$1") (pinfunction "A_P$1") (pintype "passive"))
      (node (ref "U$26") (pin "P$1") (pinfunction "A_P$1") (pintype "passive"))
      (node (ref "U$27") (pin "P$1") (pinfunction "A_P$1") (pintype "passive"))
      (node (ref "U$28") (pin "P$1") (pinfunction "A_P$1") (pintype "passive"))
      (node (ref "U$29") (pin "P$1") (pinfunction "A_P$1") (pintype "passive"))
      (node (ref "U$3") (pin "P$1") (pinfunction "A_P$1") (pintype "passive"))
      (node (ref "U$30") (pin "P$1") (pinfunction "A_P$1") (pintype "passive"))
      (node (ref "U$31") (pin "P$1") (pinfunction "A_P$1") (pintype "passive"))
      (node (ref "U$32") (pin "P$1") (pinfunction "A_P$1") (pintype "passive"))
      (node (ref "U$33") (pin "P$1") (pinfunction "A_P$1") (pintype "passive"))
      (node (ref "U$34") (pin "P$1") (pinfunction "A_P$1") (pintype "passive"))
      (node (ref "U$35") (pin "P$1") (pinfunction "A_P$1") (pintype "passive"))
      (node (ref "U$36") (pin "P$1") (pinfunction "A_P$1") (pintype "passive"))
      (node (ref "U$37") (pin "P$1") (pinfunction "A_P$1") (pintype "passive"))
      (node (ref "U$38") (pin "P$1") (pinfunction "A_P$1") (pintype "passive"))
      (node (ref "U$39") (pin "P$1") (pinfunction "A_P$1") (pintype "passive"))
      (node (ref "U$4") (pin "P$1") (pinfunction "A_P$1") (pintype "passive"))
      (node (ref "U$40") (pin "P$1") (pinfunction "A_P$1") (pintype "passive"))
      (node (ref "U$41") (pin "P$1") (pinfunction "A_P$1") (pintype "passive"))
      (node (ref "U$42") (pin "P$1") (pinfunction "A_P$1") (pintype "passive"))
      (node (ref "U$43") (pin "P$1") (pinfunction "A_P$1") (pintype "passive"))
      (node (ref "U$44") (pin "P$1") (pinfunction "A_P$1") (pintype "passive"))
      (node (ref "U$45") (pin "P$1") (pinfunction "A_P$1") (pintype "passive"))
      (node (ref "U$46") (pin "P$1") (pinfunction "A_P$1") (pintype "passive"))
      (node (ref "U$47") (pin "P$1") (pinfunction "A_P$1") (pintype "passive"))
      (node (ref "U$48") (pin "P$1") (pinfunction "A_P$1") (pintype "passive"))
      (node (ref "U$49") (pin "P$1") (pinfunction "A_P$1") (pintype "passive"))
      (node (ref "U$5") (pin "P$1") (pinfunction "A_P$1") (pintype "passive"))
      (node (ref "U$50") (pin "P$1") (pinfunction "A_P$1") (pintype "passive"))
      (node (ref "U$51") (pin "P$1") (pinfunction "A_P$1") (pintype "passive"))
      (node (ref "U$52") (pin "P$1") (pinfunction "A_P$1") (pintype "passive"))
      (node (ref "U$53") (pin "P$1") (pinfunction "A_P$1") (pintype "passive"))
      (node (ref "U$54") (pin "P$1") (pinfunction "A_P$1") (pintype "passive"))
      (node (ref "U$55") (pin "P$1") (pinfunction "A_P$1") (pintype "passive"))
      (node (ref "U$56") (pin "P$1") (pinfunction "A_P$1") (pintype "passive"))
      (node (ref "U$57") (pin "P$1") (pinfunction "A_P$1") (pintype "passive"))
      (node (ref "U$58") (pin "P$1") (pinfunction "A_P$1") (pintype "passive"))
      (node (ref "U$59") (pin "P$1") (pinfunction "A_P$1") (pintype "passive"))
      (node (ref "U$6") (pin "P$1") (pinfunction "A_P$1") (pintype "passive"))
      (node (ref "U$60") (pin "P$1") (pinfunction "A_P$1") (pintype "passive"))
      (node (ref "U$61") (pin "P$1") (pinfunction "A_P$1") (pintype "passive"))
      (node (ref "U$62") (pin "P$1") (pinfunction "A_P$1") (pintype "passive"))
      (node (ref "U$63") (pin "P$1") (pinfunction "A_P$1") (pintype "passive"))
      (node (ref "U$64") (pin "P$1") (pinfunction "A_P$1") (pintype "passive"))
      (node (ref "U$65") (pin "P$1") (pinfunction "A_P$1") (pintype "passive"))
      (node (ref "U$66") (pin "P$1") (pinfunction "A_P$1") (pintype "passive"))
      (node (ref "U$67") (pin "P$1") (pinfunction "A_P$1") (pintype "passive"))
      (node (ref "U$68") (pin "P$1") (pinfunction "A_P$1") (pintype "passive"))
      (node (ref "U$69") (pin "P$1") (pinfunction "A_P$1") (pintype "passive"))
      (node (ref "U$7") (pin "P$1") (pinfunction "A_P$1") (pintype "passive"))
      (node (ref "U$70") (pin "P$1") (pinfunction "A_P$1") (pintype "passive"))
      (node (ref "U$71") (pin "P$1") (pinfunction "A_P$1") (pintype "passive"))
      (node (ref "U$72") (pin "P$1") (pinfunction "A_P$1") (pintype "passive"))
      (node (ref "U$73") (pin "P$1") (pinfunction "A_P$1") (pintype "passive"))
      (node (ref "U$74") (pin "P$1") (pinfunction "A_P$1") (pintype "passive"))
      (node (ref "U$75") (pin "P$1") (pinfunction "A_P$1") (pintype "passive"))
      (node (ref "U$76") (pin "P$1") (pinfunction "A_P$1") (pintype "passive"))
      (node (ref "U$77") (pin "P$1") (pinfunction "A_P$1") (pintype "passive"))
      (node (ref "U$78") (pin "P$1") (pinfunction "A_P$1") (pintype "passive"))
      (node (ref "U$79") (pin "P$1") (pinfunction "A_P$1") (pintype "passive"))
      (node (ref "U$8") (pin "P$1") (pinfunction "A_P$1") (pintype "passive"))
      (node (ref "U$80") (pin "P$1") (pinfunction "A_P$1") (pintype "passive"))
      (node (ref "U$81") (pin "P$1") (pinfunction "A_P$1") (pintype "passive"))
      (node (ref "U$82") (pin "P$1") (pinfunction "A_P$1") (pintype "passive"))
      (node (ref "U$83") (pin "P$1") (pinfunction "A_P$1") (pintype "passive"))
      (node (ref "U$84") (pin "P$1") (pinfunction "A_P$1") (pintype "passive"))
      (node (ref "U$85") (pin "P$1") (pinfunction "A_P$1") (pintype "passive"))
      (node (ref "U$86") (pin "P$1") (pinfunction "A_P$1") (pintype "passive"))
      (node (ref "U$87") (pin "P$1") (pinfunction "A_P$1") (pintype "passive"))
      (node (ref "U$88") (pin "P$1") (pinfunction "A_P$1") (pintype "passive"))
      (node (ref "U$89") (pin "P$1") (pinfunction "A_P$1") (pintype "passive"))
      (node (ref "U$9") (pin "P$1") (pinfunction "A_P$1") (pintype "passive"))
      (node (ref "U$90") (pin "P$1") (pinfunction "A_P$1") (pintype "passive"))
      (node (ref "U$91") (pin "P$1") (pinfunction "A_P$1") (pintype "passive"))
      (node (ref "U$92") (pin "P$1") (pinfunction "A_P$1") (pintype "passive"))
      (node (ref "U$93") (pin "P$1") (pinfunction "A_P$1") (pintype "passive"))
      (node (ref "U$94") (pin "P$1") (pinfunction "A_P$1") (pintype "passive"))
      (node (ref "U$95") (pin "P$1") (pinfunction "A_P$1") (pintype "passive"))
      (node (ref "U$96") (pin "P$1") (pinfunction "A_P$1") (pintype "passive"))
    )
    (net (code "160") (name "unconnected-(FE01-Pad4)") (class "Default")
      (node (ref "FE01") (pin "4") (pinfunction "4_4") (pintype "passive"))
    )
    (net (code "161") (name "unconnected-(FE01-Pad14)") (class "Default")
      (node (ref "FE01") (pin "14") (pinfunction "14_14") (pintype "passive"))
    )
    (net (code "162") (name "unconnected-(FE02-Pad12)") (class "Default")
      (node (ref "FE02") (pin "12") (pinfunction "12_12") (pintype "passive"))
    )
    (net (code "163") (name "unconnected-(FE02-Pad13)") (class "Default")
      (node (ref "FE02") (pin "13") (pinfunction "13_13") (pintype "passive"))
    )
    (net (code "164") (name "unconnected-(IC1A-SOUT-Pad29)") (class "Default")
      (node (ref "IC1") (pin "29") (pinfunction "SOUT_29") (pintype "output"))
    )
    (net (code "165") (name "unconnected-(IC2A-SOUT-Pad29)") (class "Default")
      (node (ref "IC2") (pin "29") (pinfunction "SOUT_29") (pintype "output"))
    )
    (net (code "166") (name "unconnected-(IC3A-SOUT-Pad29)") (class "Default")
      (node (ref "IC3") (pin "29") (pinfunction "SOUT_29") (pintype "output"))
    )
    (net (code "167") (name "unconnected-(IC4A-SOUT-Pad29)") (class "Default")
      (node (ref "IC4") (pin "29") (pinfunction "SOUT_29") (pintype "output"))
    )
    (net (code "168") (name "unconnected-(U$97-AIO0-Pad30)") (class "Default")
      (node (ref "U$97") (pin "30") (pinfunction "AIO0_30") (pintype "bidirectional"))
    )
    (net (code "169") (name "unconnected-(U$97-AIO1-Pad35)") (class "Default")
      (node (ref "U$97") (pin "35") (pinfunction "AIO1_35") (pintype "bidirectional"))
    )
    (net (code "170") (name "unconnected-(U$97-PCMCLK-Pad7)") (class "Default")
      (node (ref "U$97") (pin "7") (pinfunction "PCMCLK_7") (pintype "bidirectional"))
    )
    (net (code "171") (name "unconnected-(U$97-PCMIN-Pad9)") (class "Default")
      (node (ref "U$97") (pin "9") (pinfunction "PCMIN_9") (pintype "bidirectional"))
    )
    (net (code "172") (name "unconnected-(U$97-PCMOUT-Pad10)") (class "Default")
      (node (ref "U$97") (pin "10") (pinfunction "PCMOUT_10") (pintype "bidirectional"))
    )
    (net (code "173") (name "unconnected-(U$97-PCMSYNC-Pad8)") (class "Default")
      (node (ref "U$97") (pin "8") (pinfunction "PCMSYNC_8") (pintype "bidirectional"))
    )
    (net (code "174") (name "unconnected-(U$97-PIO3-Pad20)") (class "Default")
      (node (ref "U$97") (pin "20") (pinfunction "PIO3_20") (pintype "bidirectional"))
    )
    (net (code "175") (name "unconnected-(U$97-PIO8-Pad31)") (class "Default")
      (node (ref "U$97") (pin "31") (pinfunction "PIO8_31") (pintype "bidirectional"))
    )
    (net (code "176") (name "unconnected-(U$97-PIO9-Pad32)") (class "Default")
      (node (ref "U$97") (pin "32") (pinfunction "PIO9_32") (pintype "bidirectional"))
    )
    (net (code "177") (name "unconnected-(U$97-PIO10-Pad33)") (class "Default")
      (node (ref "U$97") (pin "33") (pinfunction "PIO10_33") (pintype "bidirectional"))
    )
    (net (code "178") (name "unconnected-(U$97-PIO11-Pad34)") (class "Default")
      (node (ref "U$97") (pin "34") (pinfunction "PIO11_34") (pintype "bidirectional"))
    )
    (net (code "179") (name "unconnected-(U$97-RESET-Pad5)") (class "Default")
      (node (ref "U$97") (pin "5") (pinfunction "RESET_5") (pintype "bidirectional"))
    )
    (net (code "180") (name "unconnected-(U$97-USBD+-Pad17)") (class "Default")
      (node (ref "U$97") (pin "17") (pinfunction "USBD+_17") (pintype "bidirectional"))
    )
    (net (code "181") (name "unconnected-(U$97-USBD--Pad18)") (class "Default")
      (node (ref "U$97") (pin "18") (pinfunction "USBD-_18") (pintype "bidirectional"))
    )
    (net (code "182") (name "unconnected-(U$102-A-Pad1)") (class "Default")
      (node (ref "U$102") (pin "1") (pinfunction "A_1") (pintype "passive"))
    )
    (net (code "183") (name "unconnected-(U1-NC-Pad10)") (class "Default")
      (node (ref "U1") (pin "10") (pinfunction "NC_10") (pintype "passive"))
    )
    (net (code "184") (name "unconnected-(U1-RESERVED-Pad11)") (class "Default")
      (node (ref "U1") (pin "11") (pinfunction "RESERVED_11") (pintype "passive"))
    )
    (net (code "185") (name "unconnected-(U1-RESERVED_2-Pad3)") (class "Default")
      (node (ref "U1") (pin "3") (pinfunction "RESERVED_2_3") (pintype "passive"))
    )
  )
)
